# ArduinoNano33Proto-V3_0.net
KiCad netlist of a schematic drawn in EAGLE
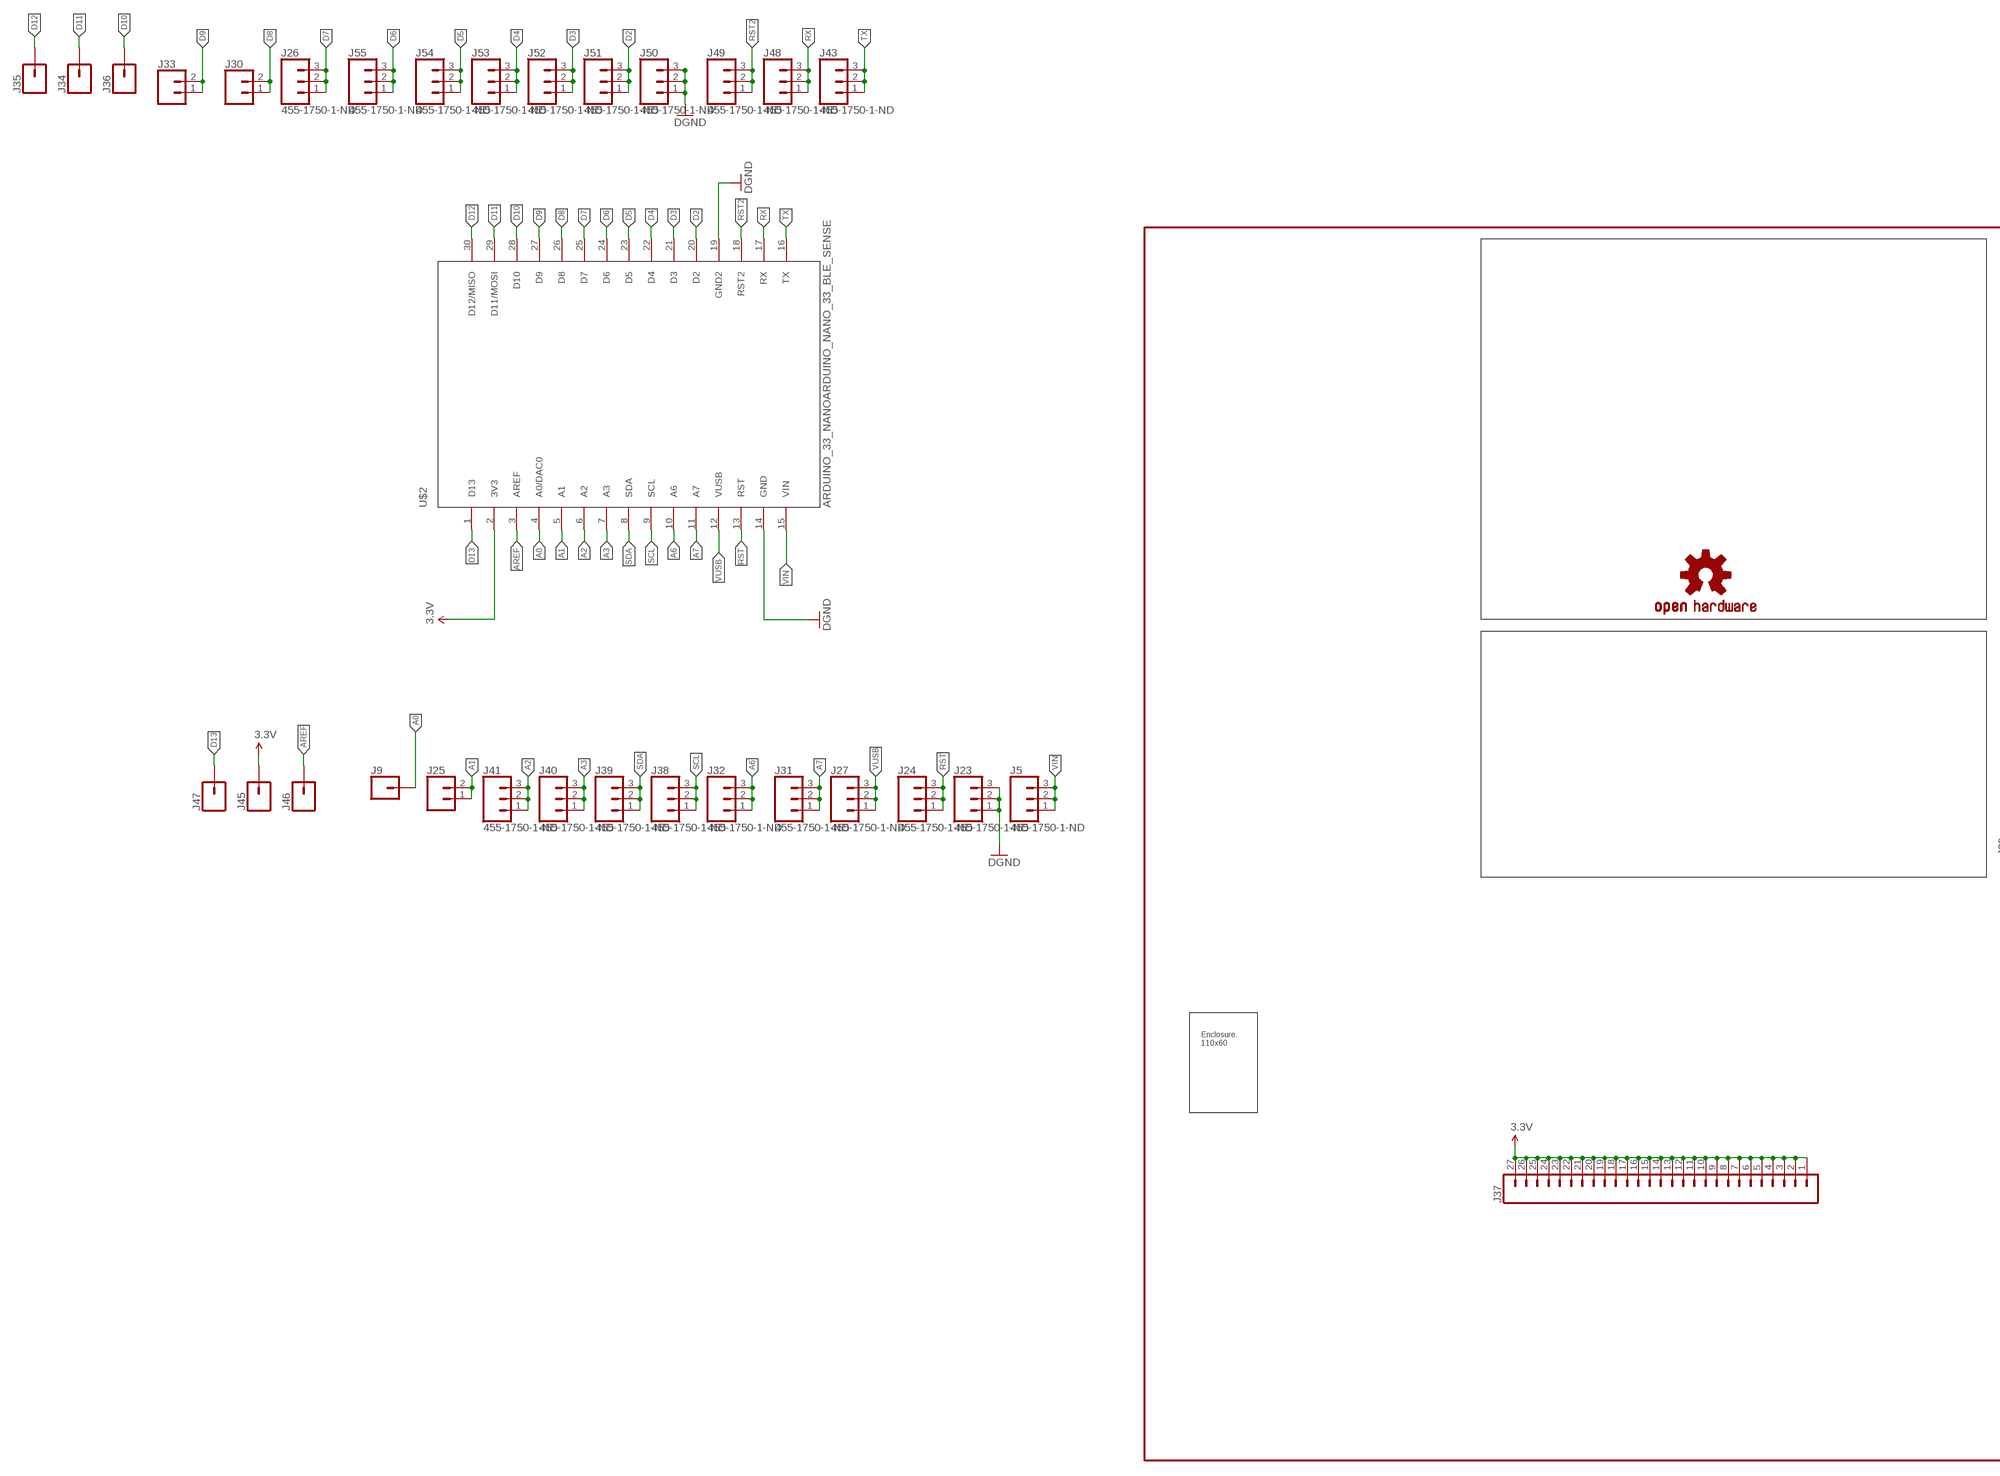
[diagram p0: schematic, sheet 1, part 1 of 2]
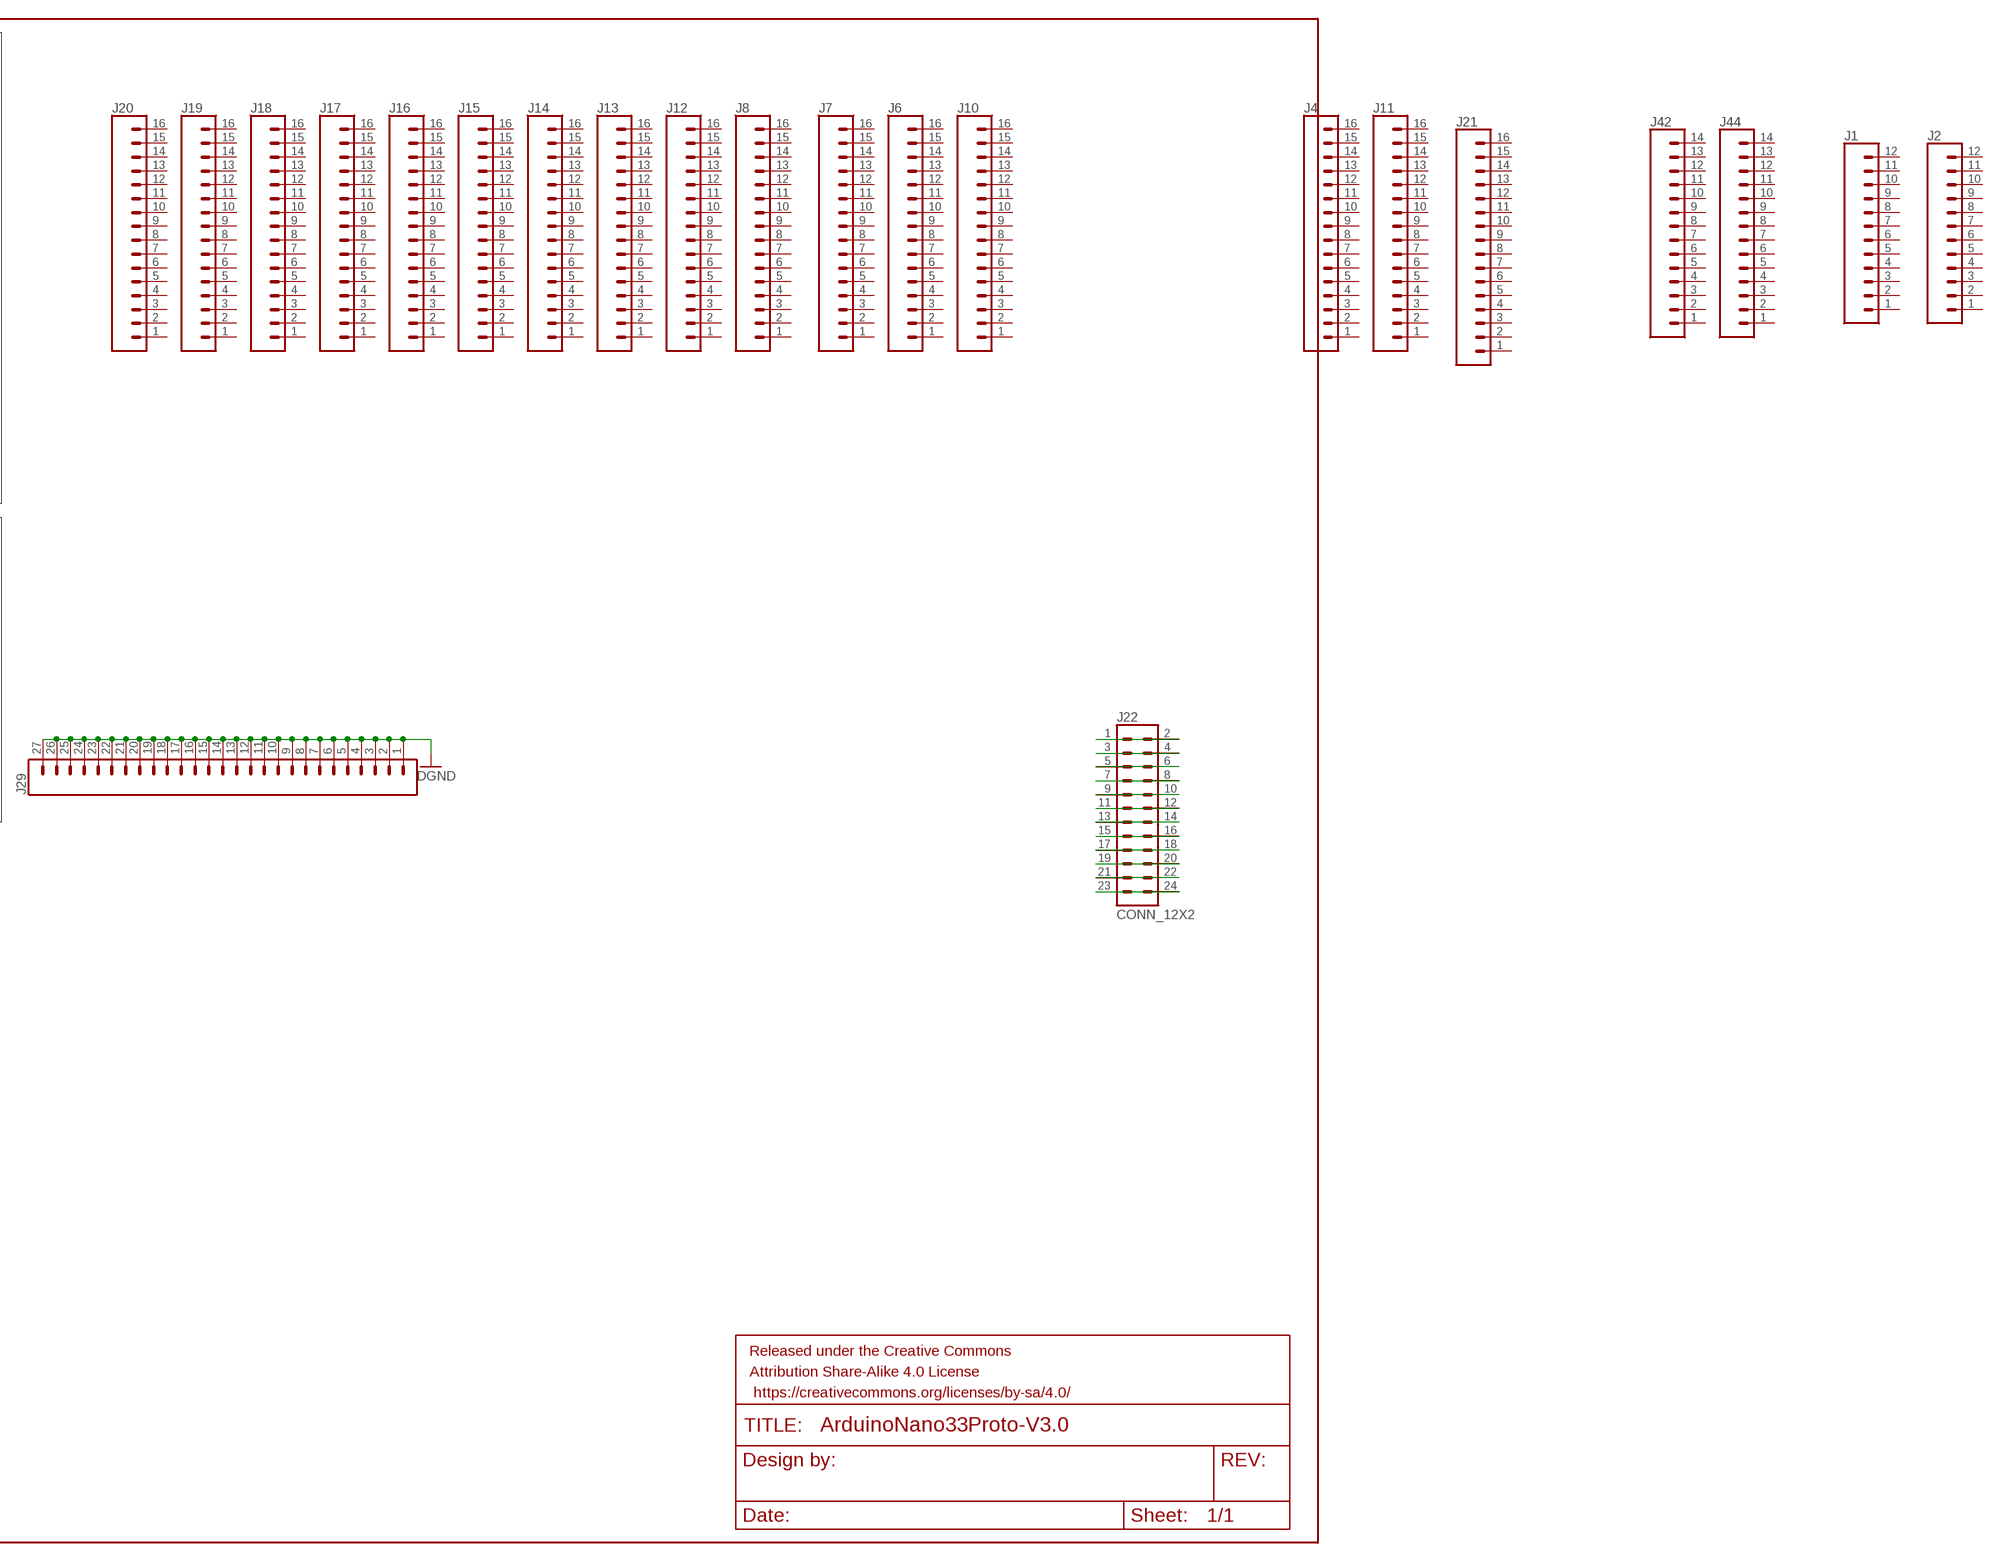
[diagram p1: schematic, sheet 1, part 2 of 2]

(export (version "E")
  (design (tool "Eeschema 10.0.6"))
  (components
    (comp (ref "FRAME2")
      (value "FRAME-LEDGER")
      (footprint "eagle-import:CREATIVE_COMMONS")
      (libsource (lib "eagle-import") (part "FRAME-LEDGER"))
    )
    (comp (ref "J1")
      (value "CONN_12NO_SILK")
      (footprint "eagle-import:1X12_NO_SILK")
      (libsource (lib "eagle-import") (part "CONN_12NO_SILK"))
    )
    (comp (ref "J2")
      (value "CONN_12NO_SILK")
      (footprint "eagle-import:1X12_NO_SILK")
      (libsource (lib "eagle-import") (part "CONN_12NO_SILK"))
    )
    (comp (ref "J4")
      (value "CONN_161X16_NO_SILK")
      (footprint "eagle-import:1X16_NO_SILK")
      (libsource (lib "eagle-import") (part "CONN_161X16_NO_SILK"))
    )
    (comp (ref "J5")
      (value "455-1750-1-ND")
      (footprint "eagle-import:1X03")
      (libsource (lib "eagle-import") (part "CONN_03"))
    )
    (comp (ref "J6")
      (value "CONN_161X16_NO_SILK")
      (footprint "eagle-import:1X16_NO_SILK")
      (libsource (lib "eagle-import") (part "CONN_161X16_NO_SILK"))
    )
    (comp (ref "J7")
      (value "CONN_161X16_NO_SILK")
      (footprint "eagle-import:1X16_NO_SILK")
      (libsource (lib "eagle-import") (part "CONN_161X16_NO_SILK"))
    )
    (comp (ref "J8")
      (value "CONN_161X16_NO_SILK")
      (footprint "eagle-import:1X16_NO_SILK")
      (libsource (lib "eagle-import") (part "CONN_161X16_NO_SILK"))
    )
    (comp (ref "J9")
      (value "CONN_01PTH_NO_SILK_YES_STOP")
      (footprint "eagle-import:1X01_NO_SILK")
      (libsource (lib "eagle-import") (part "CONN_01PTH_NO_SILK_YES_STOP"))
    )
    (comp (ref "J10")
      (value "CONN_161X16_NO_SILK")
      (footprint "eagle-import:1X16_NO_SILK")
      (libsource (lib "eagle-import") (part "CONN_161X16_NO_SILK"))
    )
    (comp (ref "J11")
      (value "CONN_161X16_NO_SILK")
      (footprint "eagle-import:1X16_NO_SILK")
      (libsource (lib "eagle-import") (part "CONN_161X16_NO_SILK"))
    )
    (comp (ref "J12")
      (value "CONN_161X16_NO_SILK")
      (footprint "eagle-import:1X16_NO_SILK")
      (libsource (lib "eagle-import") (part "CONN_161X16_NO_SILK"))
    )
    (comp (ref "J13")
      (value "CONN_161X16_NO_SILK")
      (footprint "eagle-import:1X16_NO_SILK")
      (libsource (lib "eagle-import") (part "CONN_161X16_NO_SILK"))
    )
    (comp (ref "J14")
      (value "CONN_161X16_NO_SILK")
      (footprint "eagle-import:1X16_NO_SILK")
      (libsource (lib "eagle-import") (part "CONN_161X16_NO_SILK"))
    )
    (comp (ref "J15")
      (value "CONN_161X16_NO_SILK")
      (footprint "eagle-import:1X16_NO_SILK")
      (libsource (lib "eagle-import") (part "CONN_161X16_NO_SILK"))
    )
    (comp (ref "J16")
      (value "CONN_161X16_NO_SILK")
      (footprint "eagle-import:1X16_NO_SILK")
      (libsource (lib "eagle-import") (part "CONN_161X16_NO_SILK"))
    )
    (comp (ref "J17")
      (value "CONN_161X16_NO_SILK")
      (footprint "eagle-import:1X16_NO_SILK")
      (libsource (lib "eagle-import") (part "CONN_161X16_NO_SILK"))
    )
    (comp (ref "J18")
      (value "CONN_161X16_NO_SILK")
      (footprint "eagle-import:1X16_NO_SILK")
      (libsource (lib "eagle-import") (part "CONN_161X16_NO_SILK"))
    )
    (comp (ref "J19")
      (value "CONN_161X16_NO_SILK")
      (footprint "eagle-import:1X16_NO_SILK")
      (libsource (lib "eagle-import") (part "CONN_161X16_NO_SILK"))
    )
    (comp (ref "J20")
      (value "CONN_161X16_NO_SILK")
      (footprint "eagle-import:1X16_NO_SILK")
      (libsource (lib "eagle-import") (part "CONN_161X16_NO_SILK"))
    )
    (comp (ref "J21")
      (value "CONN_161X16_NO_SILK")
      (footprint "eagle-import:1X16_NO_SILK")
      (libsource (lib "eagle-import") (part "CONN_161X16_NO_SILK"))
    )
    (comp (ref "J22")
      (value "CONN_12X2")
      (footprint "eagle-import:2X12")
      (libsource (lib "eagle-import") (part "CONN_12X2"))
    )
    (comp (ref "J23")
      (value "455-1750-1-ND")
      (footprint "eagle-import:1X03")
      (libsource (lib "eagle-import") (part "CONN_03"))
    )
    (comp (ref "J24")
      (value "455-1750-1-ND")
      (footprint "eagle-import:1X03")
      (libsource (lib "eagle-import") (part "CONN_03"))
    )
    (comp (ref "J25")
      (value "CONN_02")
      (footprint "eagle-import:1X02")
      (libsource (lib "eagle-import") (part "CONN_02"))
    )
    (comp (ref "J26")
      (value "455-1750-1-ND")
      (footprint "eagle-import:1X03")
      (libsource (lib "eagle-import") (part "CONN_03"))
    )
    (comp (ref "J27")
      (value "455-1750-1-ND")
      (footprint "eagle-import:1X03")
      (libsource (lib "eagle-import") (part "CONN_03"))
    )
    (comp (ref "J29")
      (value "CONN_27")
      (footprint "eagle-import:1X27")
      (libsource (lib "eagle-import") (part "CONN_27"))
    )
    (comp (ref "J30")
      (value "CONN_02")
      (footprint "eagle-import:1X02")
      (libsource (lib "eagle-import") (part "CONN_02"))
    )
    (comp (ref "J31")
      (value "455-1750-1-ND")
      (footprint "eagle-import:1X03")
      (libsource (lib "eagle-import") (part "CONN_03"))
    )
    (comp (ref "J32")
      (value "455-1750-1-ND")
      (footprint "eagle-import:1X03")
      (libsource (lib "eagle-import") (part "CONN_03"))
    )
    (comp (ref "J33")
      (value "CONN_02")
      (footprint "eagle-import:1X02")
      (libsource (lib "eagle-import") (part "CONN_02"))
    )
    (comp (ref "J34")
      (value "CONN_01PTH_NO_SILK_YES_STOP")
      (footprint "eagle-import:1X01_NO_SILK")
      (libsource (lib "eagle-import") (part "CONN_01PTH_NO_SILK_YES_STOP"))
    )
    (comp (ref "J35")
      (value "CONN_01PTH_NO_SILK_YES_STOP")
      (footprint "eagle-import:1X01_NO_SILK")
      (libsource (lib "eagle-import") (part "CONN_01PTH_NO_SILK_YES_STOP"))
    )
    (comp (ref "J36")
      (value "CONN_01PTH_NO_SILK_YES_STOP")
      (footprint "eagle-import:1X01_NO_SILK")
      (libsource (lib "eagle-import") (part "CONN_01PTH_NO_SILK_YES_STOP"))
    )
    (comp (ref "J37")
      (value "CONN_27")
      (footprint "eagle-import:1X27")
      (libsource (lib "eagle-import") (part "CONN_27"))
    )
    (comp (ref "J38")
      (value "455-1750-1-ND")
      (footprint "eagle-import:1X03")
      (libsource (lib "eagle-import") (part "CONN_03"))
    )
    (comp (ref "J39")
      (value "455-1750-1-ND")
      (footprint "eagle-import:1X03")
      (libsource (lib "eagle-import") (part "CONN_03"))
    )
    (comp (ref "J40")
      (value "455-1750-1-ND")
      (footprint "eagle-import:1X03")
      (libsource (lib "eagle-import") (part "CONN_03"))
    )
    (comp (ref "J41")
      (value "455-1750-1-ND")
      (footprint "eagle-import:1X03")
      (libsource (lib "eagle-import") (part "CONN_03"))
    )
    (comp (ref "J42")
      (value "CONN_14NO_SILK")
      (footprint "eagle-import:1X14_NO_SILK")
      (libsource (lib "eagle-import") (part "CONN_14NO_SILK"))
    )
    (comp (ref "J43")
      (value "455-1750-1-ND")
      (footprint "eagle-import:1X03")
      (libsource (lib "eagle-import") (part "CONN_03"))
    )
    (comp (ref "J44")
      (value "CONN_14NO_SILK")
      (footprint "eagle-import:1X14_NO_SILK")
      (libsource (lib "eagle-import") (part "CONN_14NO_SILK"))
    )
    (comp (ref "J45")
      (value "CONN_01PTH_NO_SILK_YES_STOP")
      (footprint "eagle-import:1X01_NO_SILK")
      (libsource (lib "eagle-import") (part "CONN_01PTH_NO_SILK_YES_STOP"))
    )
    (comp (ref "J46")
      (value "CONN_01PTH_NO_SILK_YES_STOP")
      (footprint "eagle-import:1X01_NO_SILK")
      (libsource (lib "eagle-import") (part "CONN_01PTH_NO_SILK_YES_STOP"))
    )
    (comp (ref "J47")
      (value "CONN_01PTH_NO_SILK_YES_STOP")
      (footprint "eagle-import:1X01_NO_SILK")
      (libsource (lib "eagle-import") (part "CONN_01PTH_NO_SILK_YES_STOP"))
    )
    (comp (ref "J48")
      (value "455-1750-1-ND")
      (footprint "eagle-import:1X03")
      (libsource (lib "eagle-import") (part "CONN_03"))
    )
    (comp (ref "J49")
      (value "455-1750-1-ND")
      (footprint "eagle-import:1X03")
      (libsource (lib "eagle-import") (part "CONN_03"))
    )
    (comp (ref "J50")
      (value "455-1750-1-ND")
      (footprint "eagle-import:1X03")
      (libsource (lib "eagle-import") (part "CONN_03"))
    )
    (comp (ref "J51")
      (value "455-1750-1-ND")
      (footprint "eagle-import:1X03")
      (libsource (lib "eagle-import") (part "CONN_03"))
    )
    (comp (ref "J52")
      (value "455-1750-1-ND")
      (footprint "eagle-import:1X03")
      (libsource (lib "eagle-import") (part "CONN_03"))
    )
    (comp (ref "J53")
      (value "455-1750-1-ND")
      (footprint "eagle-import:1X03")
      (libsource (lib "eagle-import") (part "CONN_03"))
    )
    (comp (ref "J54")
      (value "455-1750-1-ND")
      (footprint "eagle-import:1X03")
      (libsource (lib "eagle-import") (part "CONN_03"))
    )
    (comp (ref "J55")
      (value "455-1750-1-ND")
      (footprint "eagle-import:1X03")
      (libsource (lib "eagle-import") (part "CONN_03"))
    )
    (comp (ref "LOGO1")
      (value "OSHW-LOGOM")
      (footprint "eagle-import:OSHW-LOGO-M")
      (libsource (lib "eagle-import") (part "OSHW-LOGOM"))
    )
    (comp (ref "U$1")
      (value "CAMDENBOSS-ENCLOSURE-110X60BOTH-EXTENDED-WIDE")
      (footprint "eagle-import:CAMDENBOSS_ENCLOSURE_110X60_WIDE_EXTENDED")
      (libsource (lib "eagle-import") (part "CAMDENBOSS-ENCLOSURE-110X60BOTH-EXTENDED-WIDE"))
    )
    (comp (ref "U$2")
      (value "ARDUINO_33_NANOARDUINO_NANO_33_BLE_SENSE")
      (footprint "eagle-import:ARDUINO_NANO_33")
      (libsource (lib "eagle-import") (part "ARDUINO_33_NANOARDUINO_NANO_33_BLE_SENSE"))
    )
  )
  (nets
    (net (code "1") (name "3.3V") (class "Default")
      (node (ref "J37") (pin "1") (pinfunction "1_1") (pintype "passive"))
      (node (ref "J37") (pin "10") (pinfunction "10_10") (pintype "passive"))
      (node (ref "J37") (pin "11") (pinfunction "11_11") (pintype "passive"))
      (node (ref "J37") (pin "12") (pinfunction "12_12") (pintype "passive"))
      (node (ref "J37") (pin "13") (pinfunction "13_13") (pintype "passive"))
      (node (ref "J37") (pin "14") (pinfunction "14_14") (pintype "passive"))
      (node (ref "J37") (pin "15") (pinfunction "15_15") (pintype "passive"))
      (node (ref "J37") (pin "16") (pinfunction "16_16") (pintype "passive"))
      (node (ref "J37") (pin "17") (pinfunction "17_17") (pintype "passive"))
      (node (ref "J37") (pin "18") (pinfunction "18_18") (pintype "passive"))
      (node (ref "J37") (pin "19") (pinfunction "19_19") (pintype "passive"))
      (node (ref "J37") (pin "2") (pinfunction "2_2") (pintype "passive"))
      (node (ref "J37") (pin "20") (pinfunction "20_20") (pintype "passive"))
      (node (ref "J37") (pin "21") (pinfunction "21_21") (pintype "passive"))
      (node (ref "J37") (pin "22") (pinfunction "22_22") (pintype "passive"))
      (node (ref "J37") (pin "23") (pinfunction "23_23") (pintype "passive"))
      (node (ref "J37") (pin "24") (pinfunction "24_24") (pintype "passive"))
      (node (ref "J37") (pin "25") (pinfunction "25_25") (pintype "passive"))
      (node (ref "J37") (pin "26") (pinfunction "26_26") (pintype "passive"))
      (node (ref "J37") (pin "27") (pinfunction "27_27") (pintype "passive"))
      (node (ref "J37") (pin "3") (pinfunction "3_3") (pintype "passive"))
      (node (ref "J37") (pin "4") (pinfunction "4_4") (pintype "passive"))
      (node (ref "J37") (pin "5") (pinfunction "5_5") (pintype "passive"))
      (node (ref "J37") (pin "6") (pinfunction "6_6") (pintype "passive"))
      (node (ref "J37") (pin "7") (pinfunction "7_7") (pintype "passive"))
      (node (ref "J37") (pin "8") (pinfunction "8_8") (pintype "passive"))
      (node (ref "J37") (pin "9") (pinfunction "9_9") (pintype "passive"))
      (node (ref "J45") (pin "1") (pinfunction "1_1") (pintype "passive"))
      (node (ref "U$2") (pin "2") (pinfunction "3V3_2") (pintype "power_in"))
    )
    (net (code "2") (name "A0") (class "Default")
      (node (ref "J9") (pin "1") (pinfunction "1_1") (pintype "passive"))
      (node (ref "U$2") (pin "4") (pinfunction "A0/DAC0_4") (pintype "bidirectional"))
    )
    (net (code "3") (name "A1") (class "Default")
      (node (ref "J25") (pin "1") (pinfunction "1_1") (pintype "passive"))
      (node (ref "J25") (pin "2") (pinfunction "2_2") (pintype "passive"))
      (node (ref "U$2") (pin "5") (pinfunction "A1_5") (pintype "bidirectional"))
    )
    (net (code "4") (name "A2") (class "Default")
      (node (ref "J41") (pin "1") (pinfunction "1_1") (pintype "passive"))
      (node (ref "J41") (pin "2") (pinfunction "2_2") (pintype "passive"))
      (node (ref "J41") (pin "3") (pinfunction "3_3") (pintype "passive"))
      (node (ref "U$2") (pin "6") (pinfunction "A2_6") (pintype "bidirectional"))
    )
    (net (code "5") (name "A3") (class "Default")
      (node (ref "J40") (pin "1") (pinfunction "1_1") (pintype "passive"))
      (node (ref "J40") (pin "2") (pinfunction "2_2") (pintype "passive"))
      (node (ref "J40") (pin "3") (pinfunction "3_3") (pintype "passive"))
      (node (ref "U$2") (pin "7") (pinfunction "A3_7") (pintype "bidirectional"))
    )
    (net (code "6") (name "A6") (class "Default")
      (node (ref "J32") (pin "1") (pinfunction "1_1") (pintype "passive"))
      (node (ref "J32") (pin "2") (pinfunction "2_2") (pintype "passive"))
      (node (ref "J32") (pin "3") (pinfunction "3_3") (pintype "passive"))
      (node (ref "U$2") (pin "10") (pinfunction "A6_10") (pintype "bidirectional"))
    )
    (net (code "7") (name "A7") (class "Default")
      (node (ref "J31") (pin "1") (pinfunction "1_1") (pintype "passive"))
      (node (ref "J31") (pin "2") (pinfunction "2_2") (pintype "passive"))
      (node (ref "J31") (pin "3") (pinfunction "3_3") (pintype "passive"))
      (node (ref "U$2") (pin "11") (pinfunction "A7_11") (pintype "bidirectional"))
    )
    (net (code "8") (name "AREF") (class "Default")
      (node (ref "J46") (pin "1") (pinfunction "1_1") (pintype "passive"))
      (node (ref "U$2") (pin "3") (pinfunction "AREF_3") (pintype "output"))
    )
    (net (code "9") (name "D2") (class "Default")
      (node (ref "J51") (pin "1") (pinfunction "1_1") (pintype "passive"))
      (node (ref "J51") (pin "2") (pinfunction "2_2") (pintype "passive"))
      (node (ref "J51") (pin "3") (pinfunction "3_3") (pintype "passive"))
      (node (ref "U$2") (pin "20") (pinfunction "D2_20") (pintype "bidirectional"))
    )
    (net (code "10") (name "D3") (class "Default")
      (node (ref "J52") (pin "1") (pinfunction "1_1") (pintype "passive"))
      (node (ref "J52") (pin "2") (pinfunction "2_2") (pintype "passive"))
      (node (ref "J52") (pin "3") (pinfunction "3_3") (pintype "passive"))
      (node (ref "U$2") (pin "21") (pinfunction "D3_21") (pintype "bidirectional"))
    )
    (net (code "11") (name "D4") (class "Default")
      (node (ref "J53") (pin "1") (pinfunction "1_1") (pintype "passive"))
      (node (ref "J53") (pin "2") (pinfunction "2_2") (pintype "passive"))
      (node (ref "J53") (pin "3") (pinfunction "3_3") (pintype "passive"))
      (node (ref "U$2") (pin "22") (pinfunction "D4_22") (pintype "bidirectional"))
    )
    (net (code "12") (name "D5") (class "Default")
      (node (ref "J54") (pin "1") (pinfunction "1_1") (pintype "passive"))
      (node (ref "J54") (pin "2") (pinfunction "2_2") (pintype "passive"))
      (node (ref "J54") (pin "3") (pinfunction "3_3") (pintype "passive"))
      (node (ref "U$2") (pin "23") (pinfunction "D5_23") (pintype "bidirectional"))
    )
    (net (code "13") (name "D6") (class "Default")
      (node (ref "J55") (pin "1") (pinfunction "1_1") (pintype "passive"))
      (node (ref "J55") (pin "2") (pinfunction "2_2") (pintype "passive"))
      (node (ref "J55") (pin "3") (pinfunction "3_3") (pintype "passive"))
      (node (ref "U$2") (pin "24") (pinfunction "D6_24") (pintype "bidirectional"))
    )
    (net (code "14") (name "D7") (class "Default")
      (node (ref "J26") (pin "1") (pinfunction "1_1") (pintype "passive"))
      (node (ref "J26") (pin "2") (pinfunction "2_2") (pintype "passive"))
      (node (ref "J26") (pin "3") (pinfunction "3_3") (pintype "passive"))
      (node (ref "U$2") (pin "25") (pinfunction "D7_25") (pintype "bidirectional"))
    )
    (net (code "15") (name "D8") (class "Default")
      (node (ref "J30") (pin "1") (pinfunction "1_1") (pintype "passive"))
      (node (ref "J30") (pin "2") (pinfunction "2_2") (pintype "passive"))
      (node (ref "U$2") (pin "26") (pinfunction "D8_26") (pintype "bidirectional"))
    )
    (net (code "16") (name "D9") (class "Default")
      (node (ref "J33") (pin "1") (pinfunction "1_1") (pintype "passive"))
      (node (ref "J33") (pin "2") (pinfunction "2_2") (pintype "passive"))
      (node (ref "U$2") (pin "27") (pinfunction "D9_27") (pintype "bidirectional"))
    )
    (net (code "17") (name "D10") (class "Default")
      (node (ref "J36") (pin "1") (pinfunction "1_1") (pintype "passive"))
      (node (ref "U$2") (pin "28") (pinfunction "D10_28") (pintype "bidirectional"))
    )
    (net (code "18") (name "D11") (class "Default")
      (node (ref "J34") (pin "1") (pinfunction "1_1") (pintype "passive"))
      (node (ref "U$2") (pin "29") (pinfunction "D11/MOSI_29") (pintype "bidirectional"))
    )
    (net (code "19") (name "D12") (class "Default")
      (node (ref "J35") (pin "1") (pinfunction "1_1") (pintype "passive"))
      (node (ref "U$2") (pin "30") (pinfunction "D12/MISO_30") (pintype "bidirectional"))
    )
    (net (code "20") (name "D13") (class "Default")
      (node (ref "J47") (pin "1") (pinfunction "1_1") (pintype "passive"))
      (node (ref "U$2") (pin "1") (pinfunction "D13_1") (pintype "bidirectional"))
    )
    (net (code "21") (name "DGND") (class "Default")
      (node (ref "J23") (pin "1") (pinfunction "1_1") (pintype "passive"))
      (node (ref "J23") (pin "2") (pinfunction "2_2") (pintype "passive"))
      (node (ref "J23") (pin "3") (pinfunction "3_3") (pintype "passive"))
      (node (ref "J29") (pin "1") (pinfunction "1_1") (pintype "passive"))
      (node (ref "J29") (pin "10") (pinfunction "10_10") (pintype "passive"))
      (node (ref "J29") (pin "11") (pinfunction "11_11") (pintype "passive"))
      (node (ref "J29") (pin "12") (pinfunction "12_12") (pintype "passive"))
      (node (ref "J29") (pin "13") (pinfunction "13_13") (pintype "passive"))
      (node (ref "J29") (pin "14") (pinfunction "14_14") (pintype "passive"))
      (node (ref "J29") (pin "15") (pinfunction "15_15") (pintype "passive"))
      (node (ref "J29") (pin "16") (pinfunction "16_16") (pintype "passive"))
      (node (ref "J29") (pin "17") (pinfunction "17_17") (pintype "passive"))
      (node (ref "J29") (pin "18") (pinfunction "18_18") (pintype "passive"))
      (node (ref "J29") (pin "19") (pinfunction "19_19") (pintype "passive"))
      (node (ref "J29") (pin "2") (pinfunction "2_2") (pintype "passive"))
      (node (ref "J29") (pin "20") (pinfunction "20_20") (pintype "passive"))
      (node (ref "J29") (pin "21") (pinfunction "21_21") (pintype "passive"))
      (node (ref "J29") (pin "22") (pinfunction "22_22") (pintype "passive"))
      (node (ref "J29") (pin "23") (pinfunction "23_23") (pintype "passive"))
      (node (ref "J29") (pin "24") (pinfunction "24_24") (pintype "passive"))
      (node (ref "J29") (pin "25") (pinfunction "25_25") (pintype "passive"))
      (node (ref "J29") (pin "26") (pinfunction "26_26") (pintype "passive"))
      (node (ref "J29") (pin "27") (pinfunction "27_27") (pintype "passive"))
      (node (ref "J29") (pin "3") (pinfunction "3_3") (pintype "passive"))
      (node (ref "J29") (pin "4") (pinfunction "4_4") (pintype "passive"))
      (node (ref "J29") (pin "5") (pinfunction "5_5") (pintype "passive"))
      (node (ref "J29") (pin "6") (pinfunction "6_6") (pintype "passive"))
      (node (ref "J29") (pin "7") (pinfunction "7_7") (pintype "passive"))
      (node (ref "J29") (pin "8") (pinfunction "8_8") (pintype "passive"))
      (node (ref "J29") (pin "9") (pinfunction "9_9") (pintype "passive"))
      (node (ref "J50") (pin "1") (pinfunction "1_1") (pintype "passive"))
      (node (ref "J50") (pin "2") (pinfunction "2_2") (pintype "passive"))
      (node (ref "J50") (pin "3") (pinfunction "3_3") (pintype "passive"))
      (node (ref "U$2") (pin "14") (pinfunction "GND_14") (pintype "bidirectional"))
      (node (ref "U$2") (pin "19") (pinfunction "GND2_19") (pintype "bidirectional"))
    )
    (net (code "22") (name "Net-(J22-Pad1)") (class "Default")
      (node (ref "J22") (pin "1") (pinfunction "1_1") (pintype "passive"))
      (node (ref "J22") (pin "2") (pinfunction "2_2") (pintype "passive"))
    )
    (net (code "23") (name "Net-(J22-Pad3)") (class "Default")
      (node (ref "J22") (pin "3") (pinfunction "3_3") (pintype "passive"))
      (node (ref "J22") (pin "4") (pinfunction "4_4") (pintype "passive"))
    )
    (net (code "24") (name "Net-(J22-Pad5)") (class "Default")
      (node (ref "J22") (pin "5") (pinfunction "5_5") (pintype "passive"))
      (node (ref "J22") (pin "6") (pinfunction "6_6") (pintype "passive"))
    )
    (net (code "25") (name "Net-(J22-Pad7)") (class "Default")
      (node (ref "J22") (pin "7") (pinfunction "7_7") (pintype "passive"))
      (node (ref "J22") (pin "8") (pinfunction "8_8") (pintype "passive"))
    )
    (net (code "26") (name "Net-(J22-Pad10)") (class "Default")
      (node (ref "J22") (pin "10") (pinfunction "10_10") (pintype "passive"))
      (node (ref "J22") (pin "9") (pinfunction "9_9") (pintype "passive"))
    )
    (net (code "27") (name "Net-(J22-Pad11)") (class "Default")
      (node (ref "J22") (pin "11") (pinfunction "11_11") (pintype "passive"))
      (node (ref "J22") (pin "12") (pinfunction "12_12") (pintype "passive"))
    )
    (net (code "28") (name "Net-(J22-Pad13)") (class "Default")
      (node (ref "J22") (pin "13") (pinfunction "13_13") (pintype "passive"))
      (node (ref "J22") (pin "14") (pinfunction "14_14") (pintype "passive"))
    )
    (net (code "29") (name "Net-(J22-Pad15)") (class "Default")
      (node (ref "J22") (pin "15") (pinfunction "15_15") (pintype "passive"))
      (node (ref "J22") (pin "16") (pinfunction "16_16") (pintype "passive"))
    )
    (net (code "30") (name "Net-(J22-Pad17)") (class "Default")
      (node (ref "J22") (pin "17") (pinfunction "17_17") (pintype "passive"))
      (node (ref "J22") (pin "18") (pinfunction "18_18") (pintype "passive"))
    )
    (net (code "31") (name "Net-(J22-Pad19)") (class "Default")
      (node (ref "J22") (pin "19") (pinfunction "19_19") (pintype "passive"))
      (node (ref "J22") (pin "20") (pinfunction "20_20") (pintype "passive"))
    )
    (net (code "32") (name "Net-(J22-Pad21)") (class "Default")
      (node (ref "J22") (pin "21") (pinfunction "21_21") (pintype "passive"))
      (node (ref "J22") (pin "22") (pinfunction "22_22") (pintype "passive"))
    )
    (net (code "33") (name "Net-(J22-Pad23)") (class "Default")
      (node (ref "J22") (pin "23") (pinfunction "23_23") (pintype "passive"))
      (node (ref "J22") (pin "24") (pinfunction "24_24") (pintype "passive"))
    )
    (net (code "34") (name "RST") (class "Default")
      (node (ref "J24") (pin "1") (pinfunction "1_1") (pintype "passive"))
      (node (ref "J24") (pin "2") (pinfunction "2_2") (pintype "passive"))
      (node (ref "J24") (pin "3") (pinfunction "3_3") (pintype "passive"))
      (node (ref "U$2") (pin "13") (pinfunction "RST_13") (pintype "bidirectional"))
    )
    (net (code "35") (name "RST2") (class "Default")
      (node (ref "J49") (pin "1") (pinfunction "1_1") (pintype "passive"))
      (node (ref "J49") (pin "2") (pinfunction "2_2") (pintype "passive"))
      (node (ref "J49") (pin "3") (pinfunction "3_3") (pintype "passive"))
      (node (ref "U$2") (pin "18") (pinfunction "RST2_18") (pintype "bidirectional"))
    )
    (net (code "36") (name "RX") (class "Default")
      (node (ref "J48") (pin "1") (pinfunction "1_1") (pintype "passive"))
      (node (ref "J48") (pin "2") (pinfunction "2_2") (pintype "passive"))
      (node (ref "J48") (pin "3") (pinfunction "3_3") (pintype "passive"))
      (node (ref "U$2") (pin "17") (pinfunction "RX_17") (pintype "bidirectional"))
    )
    (net (code "37") (name "SCL") (class "Default")
      (node (ref "J38") (pin "1") (pinfunction "1_1") (pintype "passive"))
      (node (ref "J38") (pin "2") (pinfunction "2_2") (pintype "passive"))
      (node (ref "J38") (pin "3") (pinfunction "3_3") (pintype "passive"))
      (node (ref "U$2") (pin "9") (pinfunction "SCL_9") (pintype "bidirectional"))
    )
    (net (code "38") (name "SDA") (class "Default")
      (node (ref "J39") (pin "1") (pinfunction "1_1") (pintype "passive"))
      (node (ref "J39") (pin "2") (pinfunction "2_2") (pintype "passive"))
      (node (ref "J39") (pin "3") (pinfunction "3_3") (pintype "passive"))
      (node (ref "U$2") (pin "8") (pinfunction "SDA_8") (pintype "bidirectional"))
    )
    (net (code "39") (name "TX") (class "Default")
      (node (ref "J43") (pin "1") (pinfunction "1_1") (pintype "passive"))
      (node (ref "J43") (pin "2") (pinfunction "2_2") (pintype "passive"))
      (node (ref "J43") (pin "3") (pinfunction "3_3") (pintype "passive"))
      (node (ref "U$2") (pin "16") (pinfunction "TX_16") (pintype "bidirectional"))
    )
    (net (code "40") (name "VIN") (class "Default")
      (node (ref "J5") (pin "1") (pinfunction "1_1") (pintype "passive"))
      (node (ref "J5") (pin "2") (pinfunction "2_2") (pintype "passive"))
      (node (ref "J5") (pin "3") (pinfunction "3_3") (pintype "passive"))
      (node (ref "U$2") (pin "15") (pinfunction "VIN_15") (pintype "power_in"))
    )
    (net (code "41") (name "VUSB") (class "Default")
      (node (ref "J27") (pin "1") (pinfunction "1_1") (pintype "passive"))
      (node (ref "J27") (pin "2") (pinfunction "2_2") (pintype "passive"))
      (node (ref "J27") (pin "3") (pinfunction "3_3") (pintype "passive"))
      (node (ref "U$2") (pin "12") (pinfunction "VUSB_12") (pintype "power_in"))
    )
    (net (code "42") (name "unconnected-(J1-Pad1)") (class "Default")
      (node (ref "J1") (pin "1") (pinfunction "1_1") (pintype "passive"))
    )
    (net (code "43") (name "unconnected-(J1-Pad2)") (class "Default")
      (node (ref "J1") (pin "2") (pinfunction "2_2") (pintype "passive"))
    )
    (net (code "44") (name "unconnected-(J1-Pad3)") (class "Default")
      (node (ref "J1") (pin "3") (pinfunction "3_3") (pintype "passive"))
    )
    (net (code "45") (name "unconnected-(J1-Pad4)") (class "Default")
      (node (ref "J1") (pin "4") (pinfunction "4_4") (pintype "passive"))
    )
    (net (code "46") (name "unconnected-(J1-Pad5)") (class "Default")
      (node (ref "J1") (pin "5") (pinfunction "5_5") (pintype "passive"))
    )
    (net (code "47") (name "unconnected-(J1-Pad6)") (class "Default")
      (node (ref "J1") (pin "6") (pinfunction "6_6") (pintype "passive"))
    )
    (net (code "48") (name "unconnected-(J1-Pad7)") (class "Default")
      (node (ref "J1") (pin "7") (pinfunction "7_7") (pintype "passive"))
    )
    (net (code "49") (name "unconnected-(J1-Pad8)") (class "Default")
      (node (ref "J1") (pin "8") (pinfunction "8_8") (pintype "passive"))
    )
    (net (code "50") (name "unconnected-(J1-Pad9)") (class "Default")
      (node (ref "J1") (pin "9") (pinfunction "9_9") (pintype "passive"))
    )
    (net (code "51") (name "unconnected-(J1-Pad10)") (class "Default")
      (node (ref "J1") (pin "10") (pinfunction "10_10") (pintype "passive"))
    )
    (net (code "52") (name "unconnected-(J1-Pad11)") (class "Default")
      (node (ref "J1") (pin "11") (pinfunction "11_11") (pintype "passive"))
    )
    (net (code "53") (name "unconnected-(J1-Pad12)") (class "Default")
      (node (ref "J1") (pin "12") (pinfunction "12_12") (pintype "passive"))
    )
    (net (code "54") (name "unconnected-(J2-Pad1)") (class "Default")
      (node (ref "J2") (pin "1") (pinfunction "1_1") (pintype "passive"))
    )
    (net (code "55") (name "unconnected-(J2-Pad2)") (class "Default")
      (node (ref "J2") (pin "2") (pinfunction "2_2") (pintype "passive"))
    )
    (net (code "56") (name "unconnected-(J2-Pad3)") (class "Default")
      (node (ref "J2") (pin "3") (pinfunction "3_3") (pintype "passive"))
    )
    (net (code "57") (name "unconnected-(J2-Pad4)") (class "Default")
      (node (ref "J2") (pin "4") (pinfunction "4_4") (pintype "passive"))
    )
    (net (code "58") (name "unconnected-(J2-Pad5)") (class "Default")
      (node (ref "J2") (pin "5") (pinfunction "5_5") (pintype "passive"))
    )
    (net (code "59") (name "unconnected-(J2-Pad6)") (class "Default")
      (node (ref "J2") (pin "6") (pinfunction "6_6") (pintype "passive"))
    )
    (net (code "60") (name "unconnected-(J2-Pad7)") (class "Default")
      (node (ref "J2") (pin "7") (pinfunction "7_7") (pintype "passive"))
    )
    (net (code "61") (name "unconnected-(J2-Pad8)") (class "Default")
      (node (ref "J2") (pin "8") (pinfunction "8_8") (pintype "passive"))
    )
    (net (code "62") (name "unconnected-(J2-Pad9)") (class "Default")
      (node (ref "J2") (pin "9") (pinfunction "9_9") (pintype "passive"))
    )
    (net (code "63") (name "unconnected-(J2-Pad10)") (class "Default")
      (node (ref "J2") (pin "10") (pinfunction "10_10") (pintype "passive"))
    )
    (net (code "64") (name "unconnected-(J2-Pad11)") (class "Default")
      (node (ref "J2") (pin "11") (pinfunction "11_11") (pintype "passive"))
    )
    (net (code "65") (name "unconnected-(J2-Pad12)") (class "Default")
      (node (ref "J2") (pin "12") (pinfunction "12_12") (pintype "passive"))
    )
    (net (code "66") (name "unconnected-(J4-Pad1)") (class "Default")
      (node (ref "J4") (pin "1") (pinfunction "1_1") (pintype "passive"))
    )
    (net (code "67") (name "unconnected-(J4-Pad2)") (class "Default")
      (node (ref "J4") (pin "2") (pinfunction "2_2") (pintype "passive"))
    )
    (net (code "68") (name "unconnected-(J4-Pad3)") (class "Default")
      (node (ref "J4") (pin "3") (pinfunction "3_3") (pintype "passive"))
    )
    (net (code "69") (name "unconnected-(J4-Pad4)") (class "Default")
      (node (ref "J4") (pin "4") (pinfunction "4_4") (pintype "passive"))
    )
    (net (code "70") (name "unconnected-(J4-Pad5)") (class "Default")
      (node (ref "J4") (pin "5") (pinfunction "5_5") (pintype "passive"))
    )
    (net (code "71") (name "unconnected-(J4-Pad6)") (class "Default")
      (node (ref "J4") (pin "6") (pinfunction "6_6") (pintype "passive"))
    )
    (net (code "72") (name "unconnected-(J4-Pad7)") (class "Default")
      (node (ref "J4") (pin "7") (pinfunction "7_7") (pintype "passive"))
    )
    (net (code "73") (name "unconnected-(J4-Pad8)") (class "Default")
      (node (ref "J4") (pin "8") (pinfunction "8_8") (pintype "passive"))
    )
    (net (code "74") (name "unconnected-(J4-Pad9)") (class "Default")
      (node (ref "J4") (pin "9") (pinfunction "9_9") (pintype "passive"))
    )
    (net (code "75") (name "unconnected-(J4-Pad10)") (class "Default")
      (node (ref "J4") (pin "10") (pinfunction "10_10") (pintype "passive"))
    )
    (net (code "76") (name "unconnected-(J4-Pad11)") (class "Default")
      (node (ref "J4") (pin "11") (pinfunction "11_11") (pintype "passive"))
    )
    (net (code "77") (name "unconnected-(J4-Pad12)") (class "Default")
      (node (ref "J4") (pin "12") (pinfunction "12_12") (pintype "passive"))
    )
    (net (code "78") (name "unconnected-(J4-Pad13)") (class "Default")
      (node (ref "J4") (pin "13") (pinfunction "13_13") (pintype "passive"))
    )
    (net (code "79") (name "unconnected-(J4-Pad14)") (class "Default")
      (node (ref "J4") (pin "14") (pinfunction "14_14") (pintype "passive"))
    )
    (net (code "80") (name "unconnected-(J4-Pad15)") (class "Default")
      (node (ref "J4") (pin "15") (pinfunction "15_15") (pintype "passive"))
    )
    (net (code "81") (name "unconnected-(J4-Pad16)") (class "Default")
      (node (ref "J4") (pin "16") (pinfunction "16_16") (pintype "passive"))
    )
    (net (code "82") (name "unconnected-(J6-Pad1)") (class "Default")
      (node (ref "J6") (pin "1") (pinfunction "1_1") (pintype "passive"))
    )
    (net (code "83") (name "unconnected-(J6-Pad2)") (class "Default")
      (node (ref "J6") (pin "2") (pinfunction "2_2") (pintype "passive"))
    )
    (net (code "84") (name "unconnected-(J6-Pad3)") (class "Default")
      (node (ref "J6") (pin "3") (pinfunction "3_3") (pintype "passive"))
    )
    (net (code "85") (name "unconnected-(J6-Pad4)") (class "Default")
      (node (ref "J6") (pin "4") (pinfunction "4_4") (pintype "passive"))
    )
    (net (code "86") (name "unconnected-(J6-Pad5)") (class "Default")
      (node (ref "J6") (pin "5") (pinfunction "5_5") (pintype "passive"))
    )
    (net (code "87") (name "unconnected-(J6-Pad6)") (class "Default")
      (node (ref "J6") (pin "6") (pinfunction "6_6") (pintype "passive"))
    )
    (net (code "88") (name "unconnected-(J6-Pad7)") (class "Default")
      (node (ref "J6") (pin "7") (pinfunction "7_7") (pintype "passive"))
    )
    (net (code "89") (name "unconnected-(J6-Pad8)") (class "Default")
      (node (ref "J6") (pin "8") (pinfunction "8_8") (pintype "passive"))
    )
    (net (code "90") (name "unconnected-(J6-Pad9)") (class "Default")
      (node (ref "J6") (pin "9") (pinfunction "9_9") (pintype "passive"))
    )
    (net (code "91") (name "unconnected-(J6-Pad10)") (class "Default")
      (node (ref "J6") (pin "10") (pinfunction "10_10") (pintype "passive"))
    )
    (net (code "92") (name "unconnected-(J6-Pad11)") (class "Default")
      (node (ref "J6") (pin "11") (pinfunction "11_11") (pintype "passive"))
    )
    (net (code "93") (name "unconnected-(J6-Pad12)") (class "Default")
      (node (ref "J6") (pin "12") (pinfunction "12_12") (pintype "passive"))
    )
    (net (code "94") (name "unconnected-(J6-Pad13)") (class "Default")
      (node (ref "J6") (pin "13") (pinfunction "13_13") (pintype "passive"))
    )
    (net (code "95") (name "unconnected-(J6-Pad14)") (class "Default")
      (node (ref "J6") (pin "14") (pinfunction "14_14") (pintype "passive"))
    )
    (net (code "96") (name "unconnected-(J6-Pad15)") (class "Default")
      (node (ref "J6") (pin "15") (pinfunction "15_15") (pintype "passive"))
    )
    (net (code "97") (name "unconnected-(J6-Pad16)") (class "Default")
      (node (ref "J6") (pin "16") (pinfunction "16_16") (pintype "passive"))
    )
    (net (code "98") (name "unconnected-(J7-Pad1)") (class "Default")
      (node (ref "J7") (pin "1") (pinfunction "1_1") (pintype "passive"))
    )
    (net (code "99") (name "unconnected-(J7-Pad2)") (class "Default")
      (node (ref "J7") (pin "2") (pinfunction "2_2") (pintype "passive"))
    )
    (net (code "100") (name "unconnected-(J7-Pad3)") (class "Default")
      (node (ref "J7") (pin "3") (pinfunction "3_3") (pintype "passive"))
    )
    (net (code "101") (name "unconnected-(J7-Pad4)") (class "Default")
      (node (ref "J7") (pin "4") (pinfunction "4_4") (pintype "passive"))
    )
    (net (code "102") (name "unconnected-(J7-Pad5)") (class "Default")
      (node (ref "J7") (pin "5") (pinfunction "5_5") (pintype "passive"))
    )
    (net (code "103") (name "unconnected-(J7-Pad6)") (class "Default")
      (node (ref "J7") (pin "6") (pinfunction "6_6") (pintype "passive"))
    )
    (net (code "104") (name "unconnected-(J7-Pad7)") (class "Default")
      (node (ref "J7") (pin "7") (pinfunction "7_7") (pintype "passive"))
    )
    (net (code "105") (name "unconnected-(J7-Pad8)") (class "Default")
      (node (ref "J7") (pin "8") (pinfunction "8_8") (pintype "passive"))
    )
    (net (code "106") (name "unconnected-(J7-Pad9)") (class "Default")
      (node (ref "J7") (pin "9") (pinfunction "9_9") (pintype "passive"))
    )
    (net (code "107") (name "unconnected-(J7-Pad10)") (class "Default")
      (node (ref "J7") (pin "10") (pinfunction "10_10") (pintype "passive"))
    )
    (net (code "108") (name "unconnected-(J7-Pad11)") (class "Default")
      (node (ref "J7") (pin "11") (pinfunction "11_11") (pintype "passive"))
    )
    (net (code "109") (name "unconnected-(J7-Pad12)") (class "Default")
      (node (ref "J7") (pin "12") (pinfunction "12_12") (pintype "passive"))
    )
    (net (code "110") (name "unconnected-(J7-Pad13)") (class "Default")
      (node (ref "J7") (pin "13") (pinfunction "13_13") (pintype "passive"))
    )
    (net (code "111") (name "unconnected-(J7-Pad14)") (class "Default")
      (node (ref "J7") (pin "14") (pinfunction "14_14") (pintype "passive"))
    )
    (net (code "112") (name "unconnected-(J7-Pad15)") (class "Default")
      (node (ref "J7") (pin "15") (pinfunction "15_15") (pintype "passive"))
    )
    (net (code "113") (name "unconnected-(J7-Pad16)") (class "Default")
      (node (ref "J7") (pin "16") (pinfunction "16_16") (pintype "passive"))
    )
    (net (code "114") (name "unconnected-(J8-Pad1)") (class "Default")
      (node (ref "J8") (pin "1") (pinfunction "1_1") (pintype "passive"))
    )
    (net (code "115") (name "unconnected-(J8-Pad2)") (class "Default")
      (node (ref "J8") (pin "2") (pinfunction "2_2") (pintype "passive"))
    )
    (net (code "116") (name "unconnected-(J8-Pad3)") (class "Default")
      (node (ref "J8") (pin "3") (pinfunction "3_3") (pintype "passive"))
    )
    (net (code "117") (name "unconnected-(J8-Pad4)") (class "Default")
      (node (ref "J8") (pin "4") (pinfunction "4_4") (pintype "passive"))
    )
    (net (code "118") (name "unconnected-(J8-Pad5)") (class "Default")
      (node (ref "J8") (pin "5") (pinfunction "5_5") (pintype "passive"))
    )
    (net (code "119") (name "unconnected-(J8-Pad6)") (class "Default")
      (node (ref "J8") (pin "6") (pinfunction "6_6") (pintype "passive"))
    )
    (net (code "120") (name "unconnected-(J8-Pad7)") (class "Default")
      (node (ref "J8") (pin "7") (pinfunction "7_7") (pintype "passive"))
    )
    (net (code "121") (name "unconnected-(J8-Pad8)") (class "Default")
      (node (ref "J8") (pin "8") (pinfunction "8_8") (pintype "passive"))
    )
    (net (code "122") (name "unconnected-(J8-Pad9)") (class "Default")
      (node (ref "J8") (pin "9") (pinfunction "9_9") (pintype "passive"))
    )
    (net (code "123") (name "unconnected-(J8-Pad10)") (class "Default")
      (node (ref "J8") (pin "10") (pinfunction "10_10") (pintype "passive"))
    )
    (net (code "124") (name "unconnected-(J8-Pad11)") (class "Default")
      (node (ref "J8") (pin "11") (pinfunction "11_11") (pintype "passive"))
    )
    (net (code "125") (name "unconnected-(J8-Pad12)") (class "Default")
      (node (ref "J8") (pin "12") (pinfunction "12_12") (pintype "passive"))
    )
    (net (code "126") (name "unconnected-(J8-Pad13)") (class "Default")
      (node (ref "J8") (pin "13") (pinfunction "13_13") (pintype "passive"))
    )
    (net (code "127") (name "unconnected-(J8-Pad14)") (class "Default")
      (node (ref "J8") (pin "14") (pinfunction "14_14") (pintype "passive"))
    )
    (net (code "128") (name "unconnected-(J8-Pad15)") (class "Default")
      (node (ref "J8") (pin "15") (pinfunction "15_15") (pintype "passive"))
    )
    (net (code "129") (name "unconnected-(J8-Pad16)") (class "Default")
      (node (ref "J8") (pin "16") (pinfunction "16_16") (pintype "passive"))
    )
    (net (code "130") (name "unconnected-(J10-Pad1)") (class "Default")
      (node (ref "J10") (pin "1") (pinfunction "1_1") (pintype "passive"))
    )
    (net (code "131") (name "unconnected-(J10-Pad2)") (class "Default")
      (node (ref "J10") (pin "2") (pinfunction "2_2") (pintype "passive"))
    )
    (net (code "132") (name "unconnected-(J10-Pad3)") (class "Default")
      (node (ref "J10") (pin "3") (pinfunction "3_3") (pintype "passive"))
    )
    (net (code "133") (name "unconnected-(J10-Pad4)") (class "Default")
      (node (ref "J10") (pin "4") (pinfunction "4_4") (pintype "passive"))
    )
    (net (code "134") (name "unconnected-(J10-Pad5)") (class "Default")
      (node (ref "J10") (pin "5") (pinfunction "5_5") (pintype "passive"))
    )
    (net (code "135") (name "unconnected-(J10-Pad6)") (class "Default")
      (node (ref "J10") (pin "6") (pinfunction "6_6") (pintype "passive"))
    )
    (net (code "136") (name "unconnected-(J10-Pad7)") (class "Default")
      (node (ref "J10") (pin "7") (pinfunction "7_7") (pintype "passive"))
    )
    (net (code "137") (name "unconnected-(J10-Pad8)") (class "Default")
      (node (ref "J10") (pin "8") (pinfunction "8_8") (pintype "passive"))
    )
    (net (code "138") (name "unconnected-(J10-Pad9)") (class "Default")
      (node (ref "J10") (pin "9") (pinfunction "9_9") (pintype "passive"))
    )
    (net (code "139") (name "unconnected-(J10-Pad10)") (class "Default")
      (node (ref "J10") (pin "10") (pinfunction "10_10") (pintype "passive"))
    )
    (net (code "140") (name "unconnected-(J10-Pad11)") (class "Default")
      (node (ref "J10") (pin "11") (pinfunction "11_11") (pintype "passive"))
    )
    (net (code "141") (name "unconnected-(J10-Pad12)") (class "Default")
      (node (ref "J10") (pin "12") (pinfunction "12_12") (pintype "passive"))
    )
    (net (code "142") (name "unconnected-(J10-Pad13)") (class "Default")
      (node (ref "J10") (pin "13") (pinfunction "13_13") (pintype "passive"))
    )
    (net (code "143") (name "unconnected-(J10-Pad14)") (class "Default")
      (node (ref "J10") (pin "14") (pinfunction "14_14") (pintype "passive"))
    )
    (net (code "144") (name "unconnected-(J10-Pad15)") (class "Default")
      (node (ref "J10") (pin "15") (pinfunction "15_15") (pintype "passive"))
    )
    (net (code "145") (name "unconnected-(J10-Pad16)") (class "Default")
      (node (ref "J10") (pin "16") (pinfunction "16_16") (pintype "passive"))
    )
    (net (code "146") (name "unconnected-(J11-Pad1)") (class "Default")
      (node (ref "J11") (pin "1") (pinfunction "1_1") (pintype "passive"))
    )
    (net (code "147") (name "unconnected-(J11-Pad2)") (class "Default")
      (node (ref "J11") (pin "2") (pinfunction "2_2") (pintype "passive"))
    )
    (net (code "148") (name "unconnected-(J11-Pad3)") (class "Default")
      (node (ref "J11") (pin "3") (pinfunction "3_3") (pintype "passive"))
    )
    (net (code "149") (name "unconnected-(J11-Pad4)") (class "Default")
      (node (ref "J11") (pin "4") (pinfunction "4_4") (pintype "passive"))
    )
    (net (code "150") (name "unconnected-(J11-Pad5)") (class "Default")
      (node (ref "J11") (pin "5") (pinfunction "5_5") (pintype "passive"))
    )
    (net (code "151") (name "unconnected-(J11-Pad6)") (class "Default")
      (node (ref "J11") (pin "6") (pinfunction "6_6") (pintype "passive"))
    )
    (net (code "152") (name "unconnected-(J11-Pad7)") (class "Default")
      (node (ref "J11") (pin "7") (pinfunction "7_7") (pintype "passive"))
    )
    (net (code "153") (name "unconnected-(J11-Pad8)") (class "Default")
      (node (ref "J11") (pin "8") (pinfunction "8_8") (pintype "passive"))
    )
    (net (code "154") (name "unconnected-(J11-Pad9)") (class "Default")
      (node (ref "J11") (pin "9") (pinfunction "9_9") (pintype "passive"))
    )
    (net (code "155") (name "unconnected-(J11-Pad10)") (class "Default")
      (node (ref "J11") (pin "10") (pinfunction "10_10") (pintype "passive"))
    )
    (net (code "156") (name "unconnected-(J11-Pad11)") (class "Default")
      (node (ref "J11") (pin "11") (pinfunction "11_11") (pintype "passive"))
    )
    (net (code "157") (name "unconnected-(J11-Pad12)") (class "Default")
      (node (ref "J11") (pin "12") (pinfunction "12_12") (pintype "passive"))
    )
    (net (code "158") (name "unconnected-(J11-Pad13)") (class "Default")
      (node (ref "J11") (pin "13") (pinfunction "13_13") (pintype "passive"))
    )
    (net (code "159") (name "unconnected-(J11-Pad14)") (class "Default")
      (node (ref "J11") (pin "14") (pinfunction "14_14") (pintype "passive"))
    )
    (net (code "160") (name "unconnected-(J11-Pad15)") (class "Default")
      (node (ref "J11") (pin "15") (pinfunction "15_15") (pintype "passive"))
    )
    (net (code "161") (name "unconnected-(J11-Pad16)") (class "Default")
      (node (ref "J11") (pin "16") (pinfunction "16_16") (pintype "passive"))
    )
    (net (code "162") (name "unconnected-(J12-Pad1)") (class "Default")
      (node (ref "J12") (pin "1") (pinfunction "1_1") (pintype "passive"))
    )
    (net (code "163") (name "unconnected-(J12-Pad2)") (class "Default")
      (node (ref "J12") (pin "2") (pinfunction "2_2") (pintype "passive"))
    )
    (net (code "164") (name "unconnected-(J12-Pad3)") (class "Default")
      (node (ref "J12") (pin "3") (pinfunction "3_3") (pintype "passive"))
    )
    (net (code "165") (name "unconnected-(J12-Pad4)") (class "Default")
      (node (ref "J12") (pin "4") (pinfunction "4_4") (pintype "passive"))
    )
    (net (code "166") (name "unconnected-(J12-Pad5)") (class "Default")
      (node (ref "J12") (pin "5") (pinfunction "5_5") (pintype "passive"))
    )
    (net (code "167") (name "unconnected-(J12-Pad6)") (class "Default")
      (node (ref "J12") (pin "6") (pinfunction "6_6") (pintype "passive"))
    )
    (net (code "168") (name "unconnected-(J12-Pad7)") (class "Default")
      (node (ref "J12") (pin "7") (pinfunction "7_7") (pintype "passive"))
    )
    (net (code "169") (name "unconnected-(J12-Pad8)") (class "Default")
      (node (ref "J12") (pin "8") (pinfunction "8_8") (pintype "passive"))
    )
    (net (code "170") (name "unconnected-(J12-Pad9)") (class "Default")
      (node (ref "J12") (pin "9") (pinfunction "9_9") (pintype "passive"))
    )
    (net (code "171") (name "unconnected-(J12-Pad10)") (class "Default")
      (node (ref "J12") (pin "10") (pinfunction "10_10") (pintype "passive"))
    )
    (net (code "172") (name "unconnected-(J12-Pad11)") (class "Default")
      (node (ref "J12") (pin "11") (pinfunction "11_11") (pintype "passive"))
    )
    (net (code "173") (name "unconnected-(J12-Pad12)") (class "Default")
      (node (ref "J12") (pin "12") (pinfunction "12_12") (pintype "passive"))
    )
    (net (code "174") (name "unconnected-(J12-Pad13)") (class "Default")
      (node (ref "J12") (pin "13") (pinfunction "13_13") (pintype "passive"))
    )
    (net (code "175") (name "unconnected-(J12-Pad14)") (class "Default")
      (node (ref "J12") (pin "14") (pinfunction "14_14") (pintype "passive"))
    )
    (net (code "176") (name "unconnected-(J12-Pad15)") (class "Default")
      (node (ref "J12") (pin "15") (pinfunction "15_15") (pintype "passive"))
    )
    (net (code "177") (name "unconnected-(J12-Pad16)") (class "Default")
      (node (ref "J12") (pin "16") (pinfunction "16_16") (pintype "passive"))
    )
    (net (code "178") (name "unconnected-(J13-Pad1)") (class "Default")
      (node (ref "J13") (pin "1") (pinfunction "1_1") (pintype "passive"))
    )
    (net (code "179") (name "unconnected-(J13-Pad2)") (class "Default")
      (node (ref "J13") (pin "2") (pinfunction "2_2") (pintype "passive"))
    )
    (net (code "180") (name "unconnected-(J13-Pad3)") (class "Default")
      (node (ref "J13") (pin "3") (pinfunction "3_3") (pintype "passive"))
    )
    (net (code "181") (name "unconnected-(J13-Pad4)") (class "Default")
      (node (ref "J13") (pin "4") (pinfunction "4_4") (pintype "passive"))
    )
    (net (code "182") (name "unconnected-(J13-Pad5)") (class "Default")
      (node (ref "J13") (pin "5") (pinfunction "5_5") (pintype "passive"))
    )
    (net (code "183") (name "unconnected-(J13-Pad6)") (class "Default")
      (node (ref "J13") (pin "6") (pinfunction "6_6") (pintype "passive"))
    )
    (net (code "184") (name "unconnected-(J13-Pad7)") (class "Default")
      (node (ref "J13") (pin "7") (pinfunction "7_7") (pintype "passive"))
    )
    (net (code "185") (name "unconnected-(J13-Pad8)") (class "Default")
      (node (ref "J13") (pin "8") (pinfunction "8_8") (pintype "passive"))
    )
    (net (code "186") (name "unconnected-(J13-Pad9)") (class "Default")
      (node (ref "J13") (pin "9") (pinfunction "9_9") (pintype "passive"))
    )
    (net (code "187") (name "unconnected-(J13-Pad10)") (class "Default")
      (node (ref "J13") (pin "10") (pinfunction "10_10") (pintype "passive"))
    )
    (net (code "188") (name "unconnected-(J13-Pad11)") (class "Default")
      (node (ref "J13") (pin "11") (pinfunction "11_11") (pintype "passive"))
    )
    (net (code "189") (name "unconnected-(J13-Pad12)") (class "Default")
      (node (ref "J13") (pin "12") (pinfunction "12_12") (pintype "passive"))
    )
    (net (code "190") (name "unconnected-(J13-Pad13)") (class "Default")
      (node (ref "J13") (pin "13") (pinfunction "13_13") (pintype "passive"))
    )
    (net (code "191") (name "unconnected-(J13-Pad14)") (class "Default")
      (node (ref "J13") (pin "14") (pinfunction "14_14") (pintype "passive"))
    )
    (net (code "192") (name "unconnected-(J13-Pad15)") (class "Default")
      (node (ref "J13") (pin "15") (pinfunction "15_15") (pintype "passive"))
    )
    (net (code "193") (name "unconnected-(J13-Pad16)") (class "Default")
      (node (ref "J13") (pin "16") (pinfunction "16_16") (pintype "passive"))
    )
    (net (code "194") (name "unconnected-(J14-Pad1)") (class "Default")
      (node (ref "J14") (pin "1") (pinfunction "1_1") (pintype "passive"))
    )
    (net (code "195") (name "unconnected-(J14-Pad2)") (class "Default")
      (node (ref "J14") (pin "2") (pinfunction "2_2") (pintype "passive"))
    )
    (net (code "196") (name "unconnected-(J14-Pad3)") (class "Default")
      (node (ref "J14") (pin "3") (pinfunction "3_3") (pintype "passive"))
    )
    (net (code "197") (name "unconnected-(J14-Pad4)") (class "Default")
      (node (ref "J14") (pin "4") (pinfunction "4_4") (pintype "passive"))
    )
    (net (code "198") (name "unconnected-(J14-Pad5)") (class "Default")
      (node (ref "J14") (pin "5") (pinfunction "5_5") (pintype "passive"))
    )
    (net (code "199") (name "unconnected-(J14-Pad6)") (class "Default")
      (node (ref "J14") (pin "6") (pinfunction "6_6") (pintype "passive"))
    )
    (net (code "200") (name "unconnected-(J14-Pad7)") (class "Default")
      (node (ref "J14") (pin "7") (pinfunction "7_7") (pintype "passive"))
    )
    (net (code "201") (name "unconnected-(J14-Pad8)") (class "Default")
      (node (ref "J14") (pin "8") (pinfunction "8_8") (pintype "passive"))
    )
    (net (code "202") (name "unconnected-(J14-Pad9)") (class "Default")
      (node (ref "J14") (pin "9") (pinfunction "9_9") (pintype "passive"))
    )
    (net (code "203") (name "unconnected-(J14-Pad10)") (class "Default")
      (node (ref "J14") (pin "10") (pinfunction "10_10") (pintype "passive"))
    )
    (net (code "204") (name "unconnected-(J14-Pad11)") (class "Default")
      (node (ref "J14") (pin "11") (pinfunction "11_11") (pintype "passive"))
    )
    (net (code "205") (name "unconnected-(J14-Pad12)") (class "Default")
      (node (ref "J14") (pin "12") (pinfunction "12_12") (pintype "passive"))
    )
    (net (code "206") (name "unconnected-(J14-Pad13)") (class "Default")
      (node (ref "J14") (pin "13") (pinfunction "13_13") (pintype "passive"))
    )
    (net (code "207") (name "unconnected-(J14-Pad14)") (class "Default")
      (node (ref "J14") (pin "14") (pinfunction "14_14") (pintype "passive"))
    )
    (net (code "208") (name "unconnected-(J14-Pad15)") (class "Default")
      (node (ref "J14") (pin "15") (pinfunction "15_15") (pintype "passive"))
    )
    (net (code "209") (name "unconnected-(J14-Pad16)") (class "Default")
      (node (ref "J14") (pin "16") (pinfunction "16_16") (pintype "passive"))
    )
    (net (code "210") (name "unconnected-(J15-Pad1)") (class "Default")
      (node (ref "J15") (pin "1") (pinfunction "1_1") (pintype "passive"))
    )
    (net (code "211") (name "unconnected-(J15-Pad2)") (class "Default")
      (node (ref "J15") (pin "2") (pinfunction "2_2") (pintype "passive"))
    )
    (net (code "212") (name "unconnected-(J15-Pad3)") (class "Default")
      (node (ref "J15") (pin "3") (pinfunction "3_3") (pintype "passive"))
    )
    (net (code "213") (name "unconnected-(J15-Pad4)") (class "Default")
      (node (ref "J15") (pin "4") (pinfunction "4_4") (pintype "passive"))
    )
    (net (code "214") (name "unconnected-(J15-Pad5)") (class "Default")
      (node (ref "J15") (pin "5") (pinfunction "5_5") (pintype "passive"))
    )
    (net (code "215") (name "unconnected-(J15-Pad6)") (class "Default")
      (node (ref "J15") (pin "6") (pinfunction "6_6") (pintype "passive"))
    )
    (net (code "216") (name "unconnected-(J15-Pad7)") (class "Default")
      (node (ref "J15") (pin "7") (pinfunction "7_7") (pintype "passive"))
    )
    (net (code "217") (name "unconnected-(J15-Pad8)") (class "Default")
      (node (ref "J15") (pin "8") (pinfunction "8_8") (pintype "passive"))
    )
    (net (code "218") (name "unconnected-(J15-Pad9)") (class "Default")
      (node (ref "J15") (pin "9") (pinfunction "9_9") (pintype "passive"))
    )
    (net (code "219") (name "unconnected-(J15-Pad10)") (class "Default")
      (node (ref "J15") (pin "10") (pinfunction "10_10") (pintype "passive"))
    )
    (net (code "220") (name "unconnected-(J15-Pad11)") (class "Default")
      (node (ref "J15") (pin "11") (pinfunction "11_11") (pintype "passive"))
    )
    (net (code "221") (name "unconnected-(J15-Pad12)") (class "Default")
      (node (ref "J15") (pin "12") (pinfunction "12_12") (pintype "passive"))
    )
    (net (code "222") (name "unconnected-(J15-Pad13)") (class "Default")
      (node (ref "J15") (pin "13") (pinfunction "13_13") (pintype "passive"))
    )
    (net (code "223") (name "unconnected-(J15-Pad14)") (class "Default")
      (node (ref "J15") (pin "14") (pinfunction "14_14") (pintype "passive"))
    )
    (net (code "224") (name "unconnected-(J15-Pad15)") (class "Default")
      (node (ref "J15") (pin "15") (pinfunction "15_15") (pintype "passive"))
    )
    (net (code "225") (name "unconnected-(J15-Pad16)") (class "Default")
      (node (ref "J15") (pin "16") (pinfunction "16_16") (pintype "passive"))
    )
    (net (code "226") (name "unconnected-(J16-Pad1)") (class "Default")
      (node (ref "J16") (pin "1") (pinfunction "1_1") (pintype "passive"))
    )
    (net (code "227") (name "unconnected-(J16-Pad2)") (class "Default")
      (node (ref "J16") (pin "2") (pinfunction "2_2") (pintype "passive"))
    )
    (net (code "228") (name "unconnected-(J16-Pad3)") (class "Default")
      (node (ref "J16") (pin "3") (pinfunction "3_3") (pintype "passive"))
    )
    (net (code "229") (name "unconnected-(J16-Pad4)") (class "Default")
      (node (ref "J16") (pin "4") (pinfunction "4_4") (pintype "passive"))
    )
    (net (code "230") (name "unconnected-(J16-Pad5)") (class "Default")
      (node (ref "J16") (pin "5") (pinfunction "5_5") (pintype "passive"))
    )
    (net (code "231") (name "unconnected-(J16-Pad6)") (class "Default")
      (node (ref "J16") (pin "6") (pinfunction "6_6") (pintype "passive"))
    )
    (net (code "232") (name "unconnected-(J16-Pad7)") (class "Default")
      (node (ref "J16") (pin "7") (pinfunction "7_7") (pintype "passive"))
    )
    (net (code "233") (name "unconnected-(J16-Pad8)") (class "Default")
      (node (ref "J16") (pin "8") (pinfunction "8_8") (pintype "passive"))
    )
    (net (code "234") (name "unconnected-(J16-Pad9)") (class "Default")
      (node (ref "J16") (pin "9") (pinfunction "9_9") (pintype "passive"))
    )
    (net (code "235") (name "unconnected-(J16-Pad10)") (class "Default")
      (node (ref "J16") (pin "10") (pinfunction "10_10") (pintype "passive"))
    )
    (net (code "236") (name "unconnected-(J16-Pad11)") (class "Default")
      (node (ref "J16") (pin "11") (pinfunction "11_11") (pintype "passive"))
    )
    (net (code "237") (name "unconnected-(J16-Pad12)") (class "Default")
      (node (ref "J16") (pin "12") (pinfunction "12_12") (pintype "passive"))
    )
    (net (code "238") (name "unconnected-(J16-Pad13)") (class "Default")
      (node (ref "J16") (pin "13") (pinfunction "13_13") (pintype "passive"))
    )
    (net (code "239") (name "unconnected-(J16-Pad14)") (class "Default")
      (node (ref "J16") (pin "14") (pinfunction "14_14") (pintype "passive"))
    )
    (net (code "240") (name "unconnected-(J16-Pad15)") (class "Default")
      (node (ref "J16") (pin "15") (pinfunction "15_15") (pintype "passive"))
    )
    (net (code "241") (name "unconnected-(J16-Pad16)") (class "Default")
      (node (ref "J16") (pin "16") (pinfunction "16_16") (pintype "passive"))
    )
    (net (code "242") (name "unconnected-(J17-Pad1)") (class "Default")
      (node (ref "J17") (pin "1") (pinfunction "1_1") (pintype "passive"))
    )
    (net (code "243") (name "unconnected-(J17-Pad2)") (class "Default")
      (node (ref "J17") (pin "2") (pinfunction "2_2") (pintype "passive"))
    )
    (net (code "244") (name "unconnected-(J17-Pad3)") (class "Default")
      (node (ref "J17") (pin "3") (pinfunction "3_3") (pintype "passive"))
    )
    (net (code "245") (name "unconnected-(J17-Pad4)") (class "Default")
      (node (ref "J17") (pin "4") (pinfunction "4_4") (pintype "passive"))
    )
    (net (code "246") (name "unconnected-(J17-Pad5)") (class "Default")
      (node (ref "J17") (pin "5") (pinfunction "5_5") (pintype "passive"))
    )
    (net (code "247") (name "unconnected-(J17-Pad6)") (class "Default")
      (node (ref "J17") (pin "6") (pinfunction "6_6") (pintype "passive"))
    )
    (net (code "248") (name "unconnected-(J17-Pad7)") (class "Default")
      (node (ref "J17") (pin "7") (pinfunction "7_7") (pintype "passive"))
    )
    (net (code "249") (name "unconnected-(J17-Pad8)") (class "Default")
      (node (ref "J17") (pin "8") (pinfunction "8_8") (pintype "passive"))
    )
    (net (code "250") (name "unconnected-(J17-Pad9)") (class "Default")
      (node (ref "J17") (pin "9") (pinfunction "9_9") (pintype "passive"))
    )
    (net (code "251") (name "unconnected-(J17-Pad10)") (class "Default")
      (node (ref "J17") (pin "10") (pinfunction "10_10") (pintype "passive"))
    )
    (net (code "252") (name "unconnected-(J17-Pad11)") (class "Default")
      (node (ref "J17") (pin "11") (pinfunction "11_11") (pintype "passive"))
    )
    (net (code "253") (name "unconnected-(J17-Pad12)") (class "Default")
      (node (ref "J17") (pin "12") (pinfunction "12_12") (pintype "passive"))
    )
    (net (code "254") (name "unconnected-(J17-Pad13)") (class "Default")
      (node (ref "J17") (pin "13") (pinfunction "13_13") (pintype "passive"))
    )
    (net (code "255") (name "unconnected-(J17-Pad14)") (class "Default")
      (node (ref "J17") (pin "14") (pinfunction "14_14") (pintype "passive"))
    )
    (net (code "256") (name "unconnected-(J17-Pad15)") (class "Default")
      (node (ref "J17") (pin "15") (pinfunction "15_15") (pintype "passive"))
    )
    (net (code "257") (name "unconnected-(J17-Pad16)") (class "Default")
      (node (ref "J17") (pin "16") (pinfunction "16_16") (pintype "passive"))
    )
    (net (code "258") (name "unconnected-(J18-Pad1)") (class "Default")
      (node (ref "J18") (pin "1") (pinfunction "1_1") (pintype "passive"))
    )
    (net (code "259") (name "unconnected-(J18-Pad2)") (class "Default")
      (node (ref "J18") (pin "2") (pinfunction "2_2") (pintype "passive"))
    )
    (net (code "260") (name "unconnected-(J18-Pad3)") (class "Default")
      (node (ref "J18") (pin "3") (pinfunction "3_3") (pintype "passive"))
    )
    (net (code "261") (name "unconnected-(J18-Pad4)") (class "Default")
      (node (ref "J18") (pin "4") (pinfunction "4_4") (pintype "passive"))
    )
    (net (code "262") (name "unconnected-(J18-Pad5)") (class "Default")
      (node (ref "J18") (pin "5") (pinfunction "5_5") (pintype "passive"))
    )
    (net (code "263") (name "unconnected-(J18-Pad6)") (class "Default")
      (node (ref "J18") (pin "6") (pinfunction "6_6") (pintype "passive"))
    )
    (net (code "264") (name "unconnected-(J18-Pad7)") (class "Default")
      (node (ref "J18") (pin "7") (pinfunction "7_7") (pintype "passive"))
    )
    (net (code "265") (name "unconnected-(J18-Pad8)") (class "Default")
      (node (ref "J18") (pin "8") (pinfunction "8_8") (pintype "passive"))
    )
    (net (code "266") (name "unconnected-(J18-Pad9)") (class "Default")
      (node (ref "J18") (pin "9") (pinfunction "9_9") (pintype "passive"))
    )
    (net (code "267") (name "unconnected-(J18-Pad10)") (class "Default")
      (node (ref "J18") (pin "10") (pinfunction "10_10") (pintype "passive"))
    )
    (net (code "268") (name "unconnected-(J18-Pad11)") (class "Default")
      (node (ref "J18") (pin "11") (pinfunction "11_11") (pintype "passive"))
    )
    (net (code "269") (name "unconnected-(J18-Pad12)") (class "Default")
      (node (ref "J18") (pin "12") (pinfunction "12_12") (pintype "passive"))
    )
    (net (code "270") (name "unconnected-(J18-Pad13)") (class "Default")
      (node (ref "J18") (pin "13") (pinfunction "13_13") (pintype "passive"))
    )
    (net (code "271") (name "unconnected-(J18-Pad14)") (class "Default")
      (node (ref "J18") (pin "14") (pinfunction "14_14") (pintype "passive"))
    )
    (net (code "272") (name "unconnected-(J18-Pad15)") (class "Default")
      (node (ref "J18") (pin "15") (pinfunction "15_15") (pintype "passive"))
    )
    (net (code "273") (name "unconnected-(J18-Pad16)") (class "Default")
      (node (ref "J18") (pin "16") (pinfunction "16_16") (pintype "passive"))
    )
    (net (code "274") (name "unconnected-(J19-Pad1)") (class "Default")
      (node (ref "J19") (pin "1") (pinfunction "1_1") (pintype "passive"))
    )
    (net (code "275") (name "unconnected-(J19-Pad2)") (class "Default")
      (node (ref "J19") (pin "2") (pinfunction "2_2") (pintype "passive"))
    )
    (net (code "276") (name "unconnected-(J19-Pad3)") (class "Default")
      (node (ref "J19") (pin "3") (pinfunction "3_3") (pintype "passive"))
    )
    (net (code "277") (name "unconnected-(J19-Pad4)") (class "Default")
      (node (ref "J19") (pin "4") (pinfunction "4_4") (pintype "passive"))
    )
    (net (code "278") (name "unconnected-(J19-Pad5)") (class "Default")
      (node (ref "J19") (pin "5") (pinfunction "5_5") (pintype "passive"))
    )
    (net (code "279") (name "unconnected-(J19-Pad6)") (class "Default")
      (node (ref "J19") (pin "6") (pinfunction "6_6") (pintype "passive"))
    )
    (net (code "280") (name "unconnected-(J19-Pad7)") (class "Default")
      (node (ref "J19") (pin "7") (pinfunction "7_7") (pintype "passive"))
    )
    (net (code "281") (name "unconnected-(J19-Pad8)") (class "Default")
      (node (ref "J19") (pin "8") (pinfunction "8_8") (pintype "passive"))
    )
    (net (code "282") (name "unconnected-(J19-Pad9)") (class "Default")
      (node (ref "J19") (pin "9") (pinfunction "9_9") (pintype "passive"))
    )
    (net (code "283") (name "unconnected-(J19-Pad10)") (class "Default")
      (node (ref "J19") (pin "10") (pinfunction "10_10") (pintype "passive"))
    )
    (net (code "284") (name "unconnected-(J19-Pad11)") (class "Default")
      (node (ref "J19") (pin "11") (pinfunction "11_11") (pintype "passive"))
    )
    (net (code "285") (name "unconnected-(J19-Pad12)") (class "Default")
      (node (ref "J19") (pin "12") (pinfunction "12_12") (pintype "passive"))
    )
    (net (code "286") (name "unconnected-(J19-Pad13)") (class "Default")
      (node (ref "J19") (pin "13") (pinfunction "13_13") (pintype "passive"))
    )
    (net (code "287") (name "unconnected-(J19-Pad14)") (class "Default")
      (node (ref "J19") (pin "14") (pinfunction "14_14") (pintype "passive"))
    )
    (net (code "288") (name "unconnected-(J19-Pad15)") (class "Default")
      (node (ref "J19") (pin "15") (pinfunction "15_15") (pintype "passive"))
    )
    (net (code "289") (name "unconnected-(J19-Pad16)") (class "Default")
      (node (ref "J19") (pin "16") (pinfunction "16_16") (pintype "passive"))
    )
    (net (code "290") (name "unconnected-(J20-Pad1)") (class "Default")
      (node (ref "J20") (pin "1") (pinfunction "1_1") (pintype "passive"))
    )
    (net (code "291") (name "unconnected-(J20-Pad2)") (class "Default")
      (node (ref "J20") (pin "2") (pinfunction "2_2") (pintype "passive"))
    )
    (net (code "292") (name "unconnected-(J20-Pad3)") (class "Default")
      (node (ref "J20") (pin "3") (pinfunction "3_3") (pintype "passive"))
    )
    (net (code "293") (name "unconnected-(J20-Pad4)") (class "Default")
      (node (ref "J20") (pin "4") (pinfunction "4_4") (pintype "passive"))
    )
    (net (code "294") (name "unconnected-(J20-Pad5)") (class "Default")
      (node (ref "J20") (pin "5") (pinfunction "5_5") (pintype "passive"))
    )
    (net (code "295") (name "unconnected-(J20-Pad6)") (class "Default")
      (node (ref "J20") (pin "6") (pinfunction "6_6") (pintype "passive"))
    )
    (net (code "296") (name "unconnected-(J20-Pad7)") (class "Default")
      (node (ref "J20") (pin "7") (pinfunction "7_7") (pintype "passive"))
    )
    (net (code "297") (name "unconnected-(J20-Pad8)") (class "Default")
      (node (ref "J20") (pin "8") (pinfunction "8_8") (pintype "passive"))
    )
    (net (code "298") (name "unconnected-(J20-Pad9)") (class "Default")
      (node (ref "J20") (pin "9") (pinfunction "9_9") (pintype "passive"))
    )
    (net (code "299") (name "unconnected-(J20-Pad10)") (class "Default")
      (node (ref "J20") (pin "10") (pinfunction "10_10") (pintype "passive"))
    )
    (net (code "300") (name "unconnected-(J20-Pad11)") (class "Default")
      (node (ref "J20") (pin "11") (pinfunction "11_11") (pintype "passive"))
    )
    (net (code "301") (name "unconnected-(J20-Pad12)") (class "Default")
      (node (ref "J20") (pin "12") (pinfunction "12_12") (pintype "passive"))
    )
    (net (code "302") (name "unconnected-(J20-Pad13)") (class "Default")
      (node (ref "J20") (pin "13") (pinfunction "13_13") (pintype "passive"))
    )
    (net (code "303") (name "unconnected-(J20-Pad14)") (class "Default")
      (node (ref "J20") (pin "14") (pinfunction "14_14") (pintype "passive"))
    )
    (net (code "304") (name "unconnected-(J20-Pad15)") (class "Default")
      (node (ref "J20") (pin "15") (pinfunction "15_15") (pintype "passive"))
    )
    (net (code "305") (name "unconnected-(J20-Pad16)") (class "Default")
      (node (ref "J20") (pin "16") (pinfunction "16_16") (pintype "passive"))
    )
    (net (code "306") (name "unconnected-(J21-Pad1)") (class "Default")
      (node (ref "J21") (pin "1") (pinfunction "1_1") (pintype "passive"))
    )
    (net (code "307") (name "unconnected-(J21-Pad2)") (class "Default")
      (node (ref "J21") (pin "2") (pinfunction "2_2") (pintype "passive"))
    )
    (net (code "308") (name "unconnected-(J21-Pad3)") (class "Default")
      (node (ref "J21") (pin "3") (pinfunction "3_3") (pintype "passive"))
    )
    (net (code "309") (name "unconnected-(J21-Pad4)") (class "Default")
      (node (ref "J21") (pin "4") (pinfunction "4_4") (pintype "passive"))
    )
    (net (code "310") (name "unconnected-(J21-Pad5)") (class "Default")
      (node (ref "J21") (pin "5") (pinfunction "5_5") (pintype "passive"))
    )
    (net (code "311") (name "unconnected-(J21-Pad6)") (class "Default")
      (node (ref "J21") (pin "6") (pinfunction "6_6") (pintype "passive"))
    )
    (net (code "312") (name "unconnected-(J21-Pad7)") (class "Default")
      (node (ref "J21") (pin "7") (pinfunction "7_7") (pintype "passive"))
    )
    (net (code "313") (name "unconnected-(J21-Pad8)") (class "Default")
      (node (ref "J21") (pin "8") (pinfunction "8_8") (pintype "passive"))
    )
    (net (code "314") (name "unconnected-(J21-Pad9)") (class "Default")
      (node (ref "J21") (pin "9") (pinfunction "9_9") (pintype "passive"))
    )
    (net (code "315") (name "unconnected-(J21-Pad10)") (class "Default")
      (node (ref "J21") (pin "10") (pinfunction "10_10") (pintype "passive"))
    )
    (net (code "316") (name "unconnected-(J21-Pad11)") (class "Default")
      (node (ref "J21") (pin "11") (pinfunction "11_11") (pintype "passive"))
    )
    (net (code "317") (name "unconnected-(J21-Pad12)") (class "Default")
      (node (ref "J21") (pin "12") (pinfunction "12_12") (pintype "passive"))
    )
    (net (code "318") (name "unconnected-(J21-Pad13)") (class "Default")
      (node (ref "J21") (pin "13") (pinfunction "13_13") (pintype "passive"))
    )
    (net (code "319") (name "unconnected-(J21-Pad14)") (class "Default")
      (node (ref "J21") (pin "14") (pinfunction "14_14") (pintype "passive"))
    )
    (net (code "320") (name "unconnected-(J21-Pad15)") (class "Default")
      (node (ref "J21") (pin "15") (pinfunction "15_15") (pintype "passive"))
    )
    (net (code "321") (name "unconnected-(J21-Pad16)") (class "Default")
      (node (ref "J21") (pin "16") (pinfunction "16_16") (pintype "passive"))
    )
    (net (code "322") (name "unconnected-(J42-Pad1)") (class "Default")
      (node (ref "J42") (pin "1") (pinfunction "1_1") (pintype "passive"))
    )
    (net (code "323") (name "unconnected-(J42-Pad2)") (class "Default")
      (node (ref "J42") (pin "2") (pinfunction "2_2") (pintype "passive"))
    )
    (net (code "324") (name "unconnected-(J42-Pad3)") (class "Default")
      (node (ref "J42") (pin "3") (pinfunction "3_3") (pintype "passive"))
    )
    (net (code "325") (name "unconnected-(J42-Pad4)") (class "Default")
      (node (ref "J42") (pin "4") (pinfunction "4_4") (pintype "passive"))
    )
    (net (code "326") (name "unconnected-(J42-Pad5)") (class "Default")
      (node (ref "J42") (pin "5") (pinfunction "5_5") (pintype "passive"))
    )
    (net (code "327") (name "unconnected-(J42-Pad6)") (class "Default")
      (node (ref "J42") (pin "6") (pinfunction "6_6") (pintype "passive"))
    )
    (net (code "328") (name "unconnected-(J42-Pad7)") (class "Default")
      (node (ref "J42") (pin "7") (pinfunction "7_7") (pintype "passive"))
    )
    (net (code "329") (name "unconnected-(J42-Pad8)") (class "Default")
      (node (ref "J42") (pin "8") (pinfunction "8_8") (pintype "passive"))
    )
    (net (code "330") (name "unconnected-(J42-Pad9)") (class "Default")
      (node (ref "J42") (pin "9") (pinfunction "9_9") (pintype "passive"))
    )
    (net (code "331") (name "unconnected-(J42-Pad10)") (class "Default")
      (node (ref "J42") (pin "10") (pinfunction "10_10") (pintype "passive"))
    )
    (net (code "332") (name "unconnected-(J42-Pad11)") (class "Default")
      (node (ref "J42") (pin "11") (pinfunction "11_11") (pintype "passive"))
    )
    (net (code "333") (name "unconnected-(J42-Pad12)") (class "Default")
      (node (ref "J42") (pin "12") (pinfunction "12_12") (pintype "passive"))
    )
    (net (code "334") (name "unconnected-(J42-Pad13)") (class "Default")
      (node (ref "J42") (pin "13") (pinfunction "13_13") (pintype "passive"))
    )
    (net (code "335") (name "unconnected-(J42-Pad14)") (class "Default")
      (node (ref "J42") (pin "14") (pinfunction "14_14") (pintype "passive"))
    )
    (net (code "336") (name "unconnected-(J44-Pad1)") (class "Default")
      (node (ref "J44") (pin "1") (pinfunction "1_1") (pintype "passive"))
    )
    (net (code "337") (name "unconnected-(J44-Pad2)") (class "Default")
      (node (ref "J44") (pin "2") (pinfunction "2_2") (pintype "passive"))
    )
    (net (code "338") (name "unconnected-(J44-Pad3)") (class "Default")
      (node (ref "J44") (pin "3") (pinfunction "3_3") (pintype "passive"))
    )
    (net (code "339") (name "unconnected-(J44-Pad4)") (class "Default")
      (node (ref "J44") (pin "4") (pinfunction "4_4") (pintype "passive"))
    )
    (net (code "340") (name "unconnected-(J44-Pad5)") (class "Default")
      (node (ref "J44") (pin "5") (pinfunction "5_5") (pintype "passive"))
    )
    (net (code "341") (name "unconnected-(J44-Pad6)") (class "Default")
      (node (ref "J44") (pin "6") (pinfunction "6_6") (pintype "passive"))
    )
    (net (code "342") (name "unconnected-(J44-Pad7)") (class "Default")
      (node (ref "J44") (pin "7") (pinfunction "7_7") (pintype "passive"))
    )
    (net (code "343") (name "unconnected-(J44-Pad8)") (class "Default")
      (node (ref "J44") (pin "8") (pinfunction "8_8") (pintype "passive"))
    )
    (net (code "344") (name "unconnected-(J44-Pad9)") (class "Default")
      (node (ref "J44") (pin "9") (pinfunction "9_9") (pintype "passive"))
    )
    (net (code "345") (name "unconnected-(J44-Pad10)") (class "Default")
      (node (ref "J44") (pin "10") (pinfunction "10_10") (pintype "passive"))
    )
    (net (code "346") (name "unconnected-(J44-Pad11)") (class "Default")
      (node (ref "J44") (pin "11") (pinfunction "11_11") (pintype "passive"))
    )
    (net (code "347") (name "unconnected-(J44-Pad12)") (class "Default")
      (node (ref "J44") (pin "12") (pinfunction "12_12") (pintype "passive"))
    )
    (net (code "348") (name "unconnected-(J44-Pad13)") (class "Default")
      (node (ref "J44") (pin "13") (pinfunction "13_13") (pintype "passive"))
    )
    (net (code "349") (name "unconnected-(J44-Pad14)") (class "Default")
      (node (ref "J44") (pin "14") (pinfunction "14_14") (pintype "passive"))
    )
  )
)
